# OctoSlime_Base_Unit.net
KiCad netlist of a schematic drawn in EasyEDA Pro
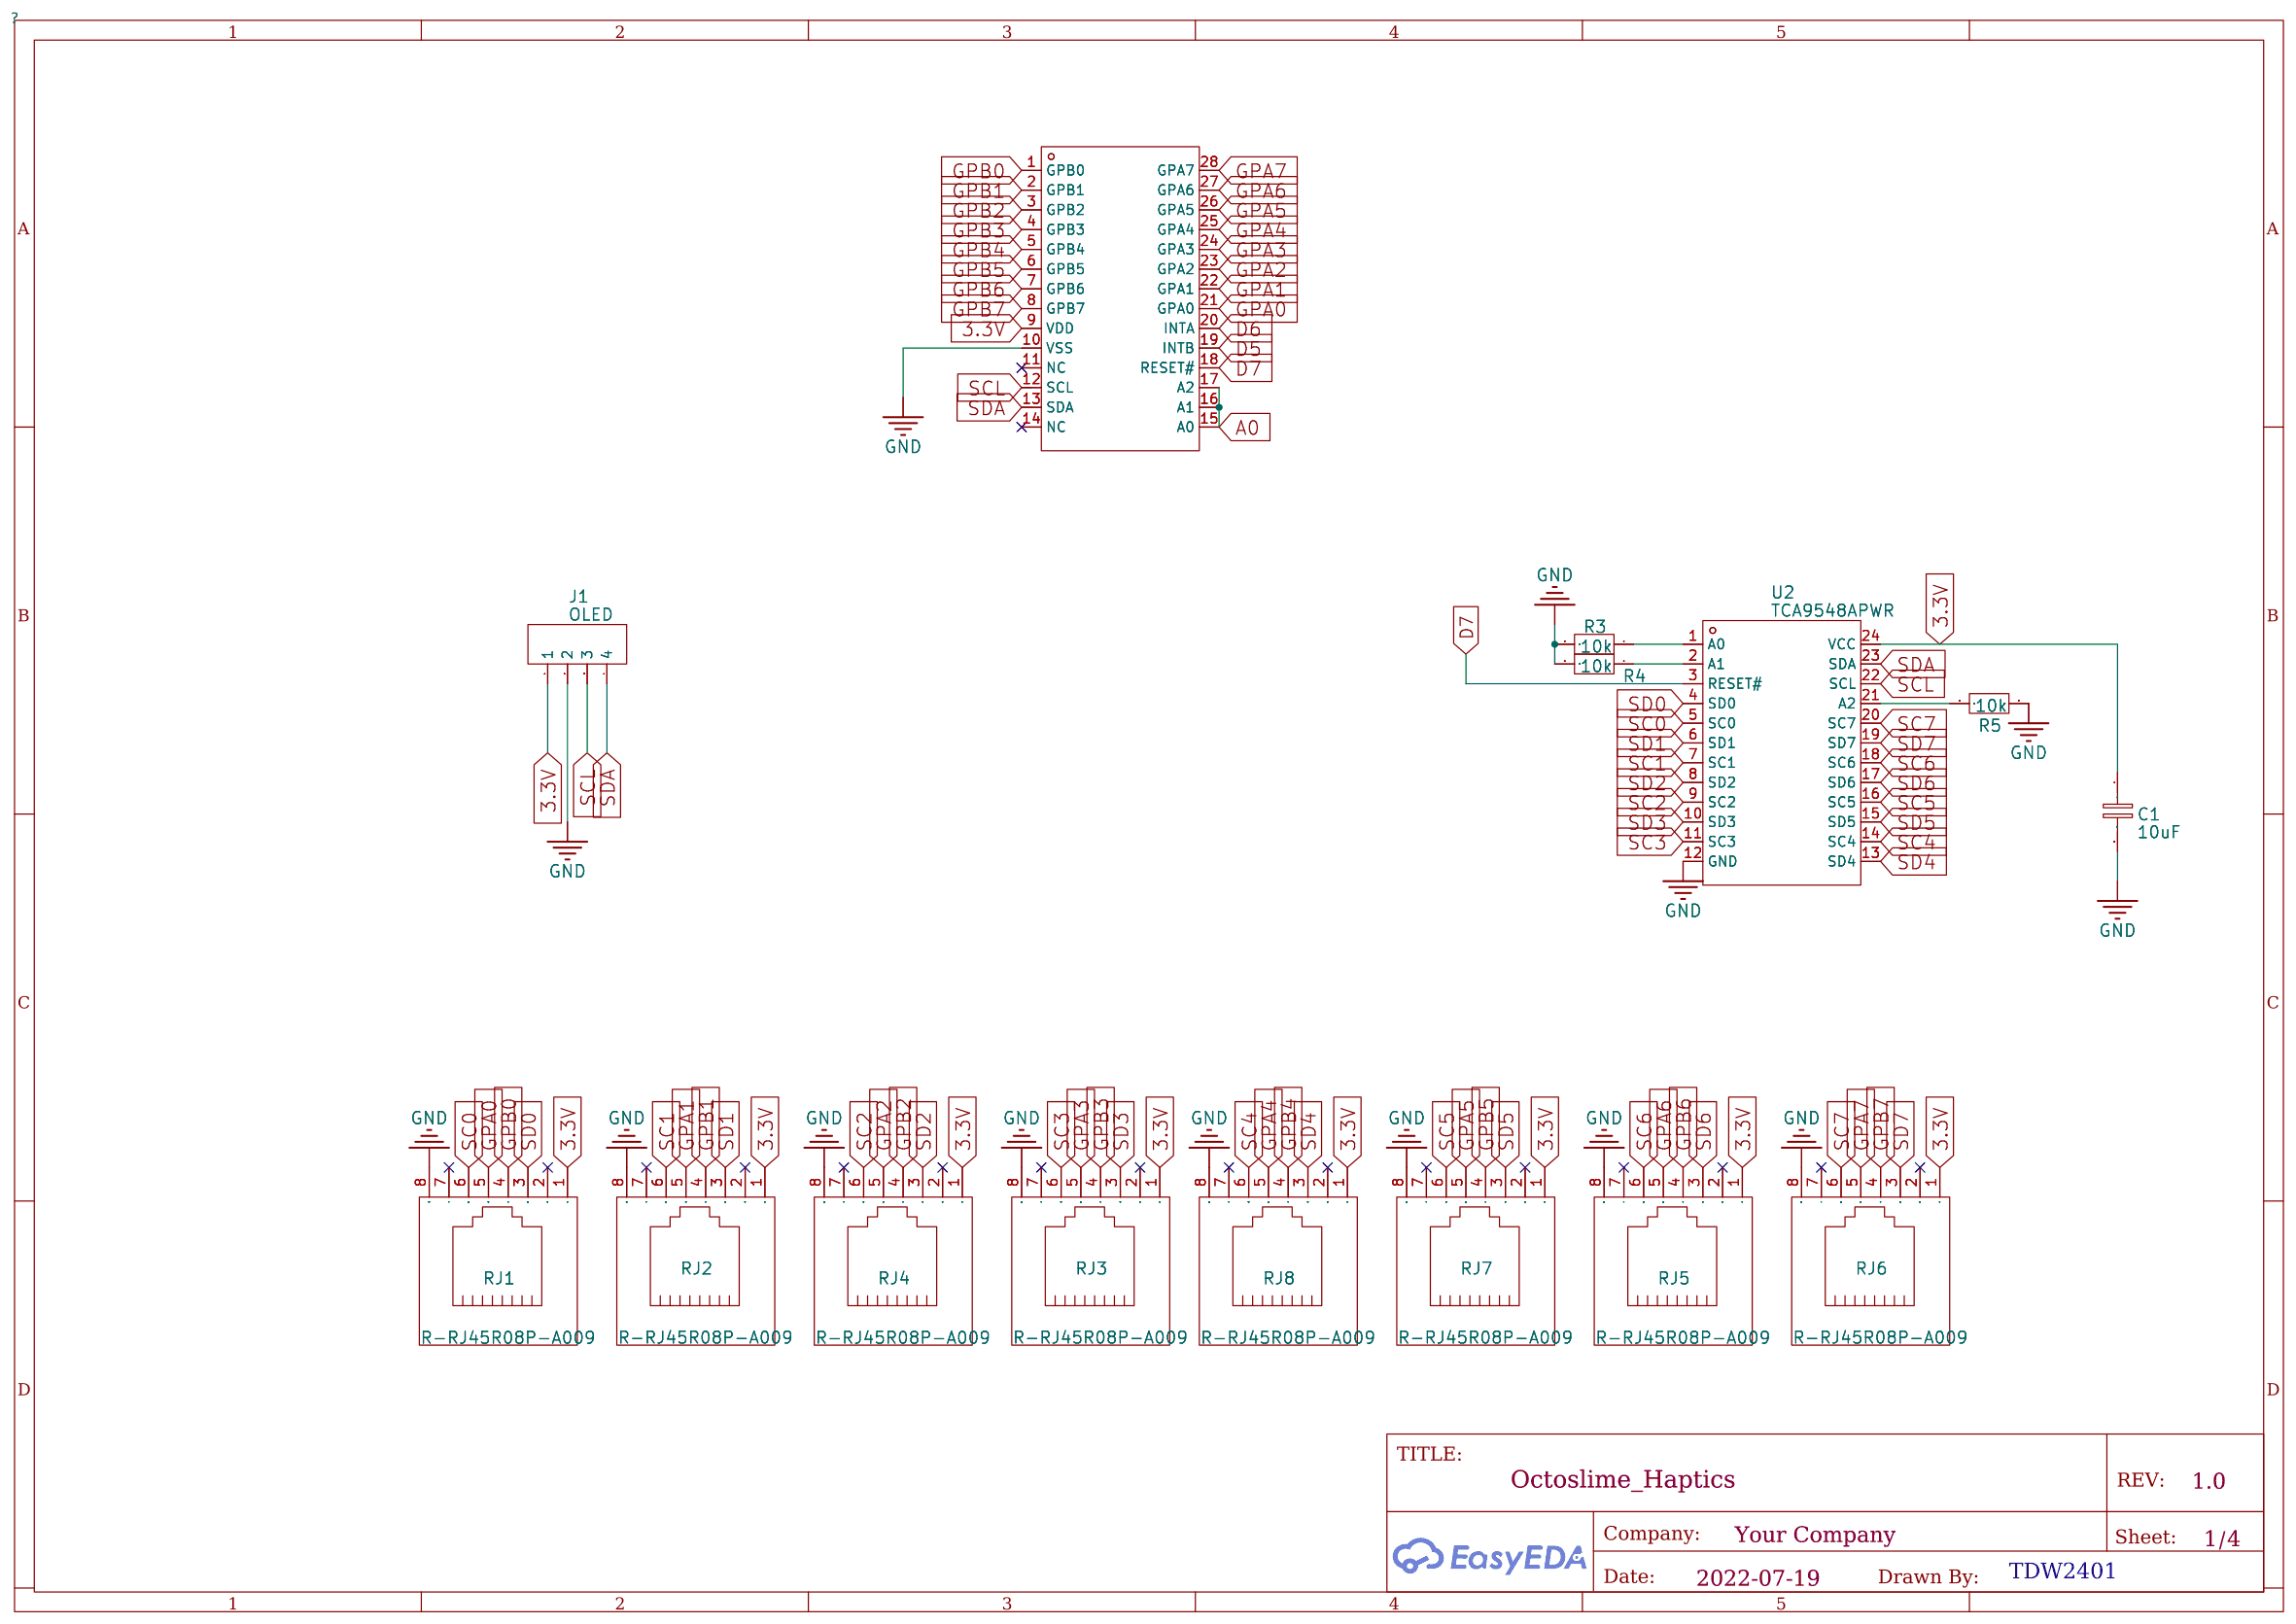
[diagram p0: I2C breakout and OLED]
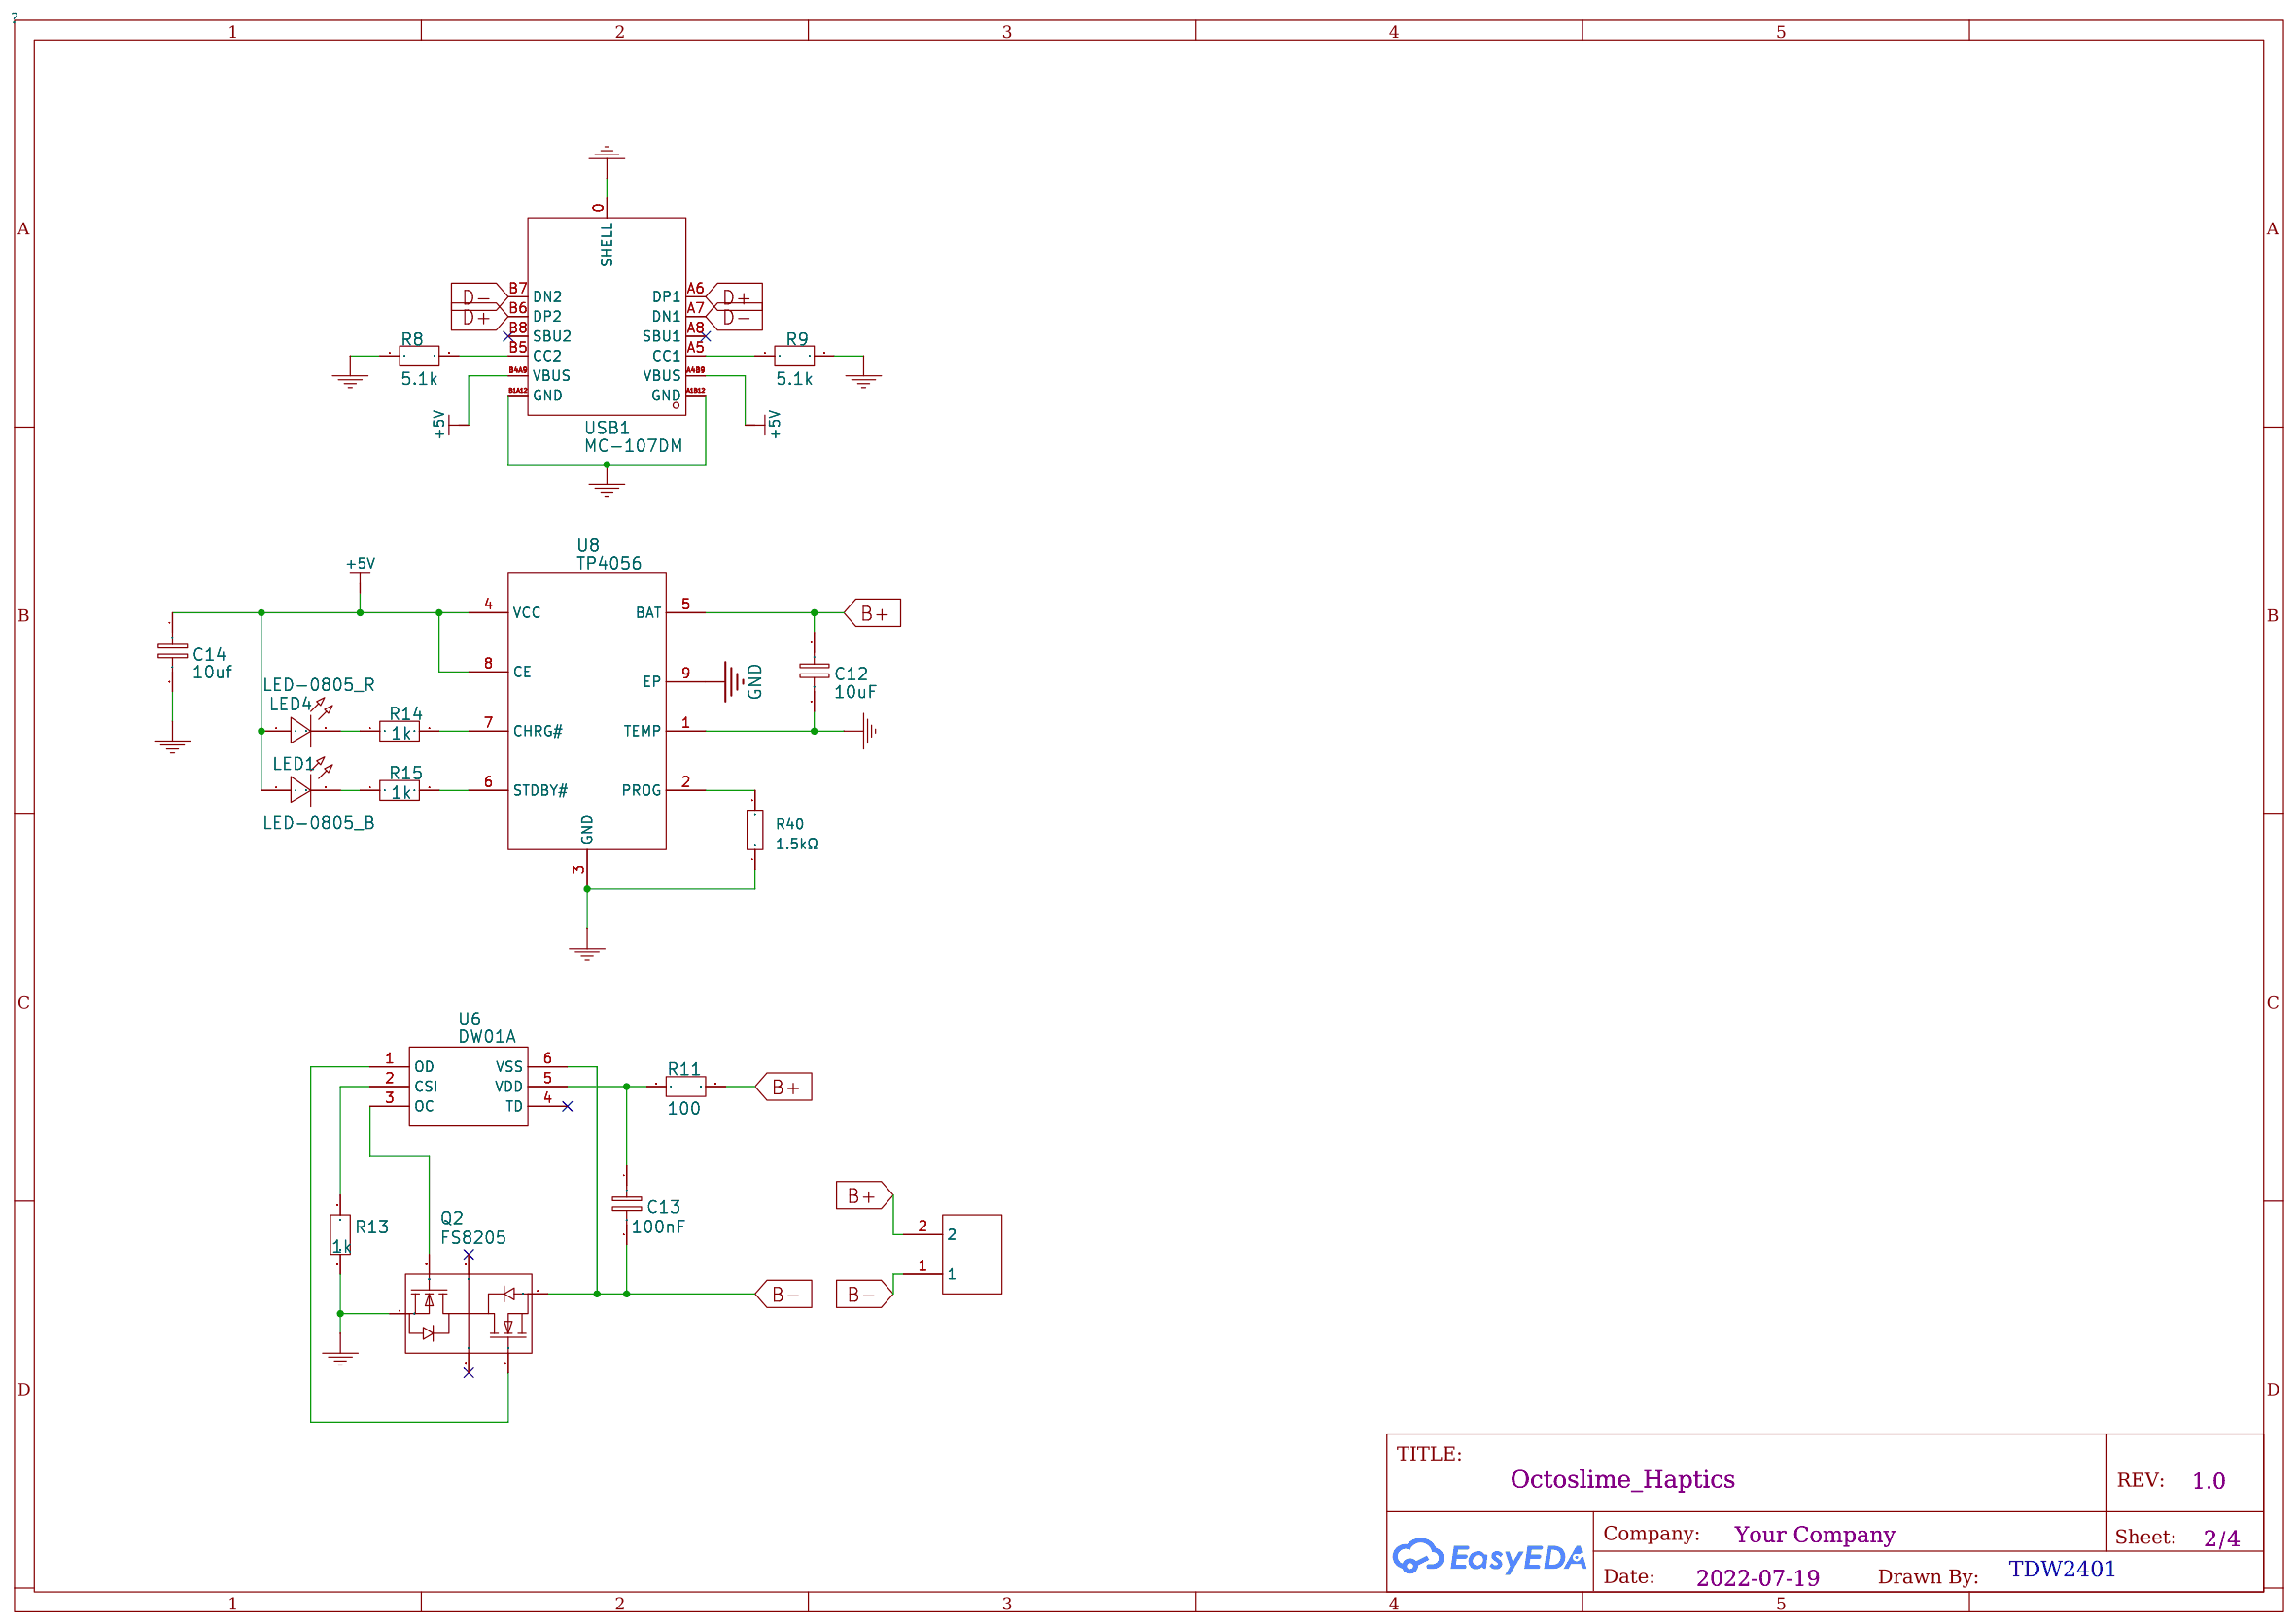
[diagram p1: Charge / data]
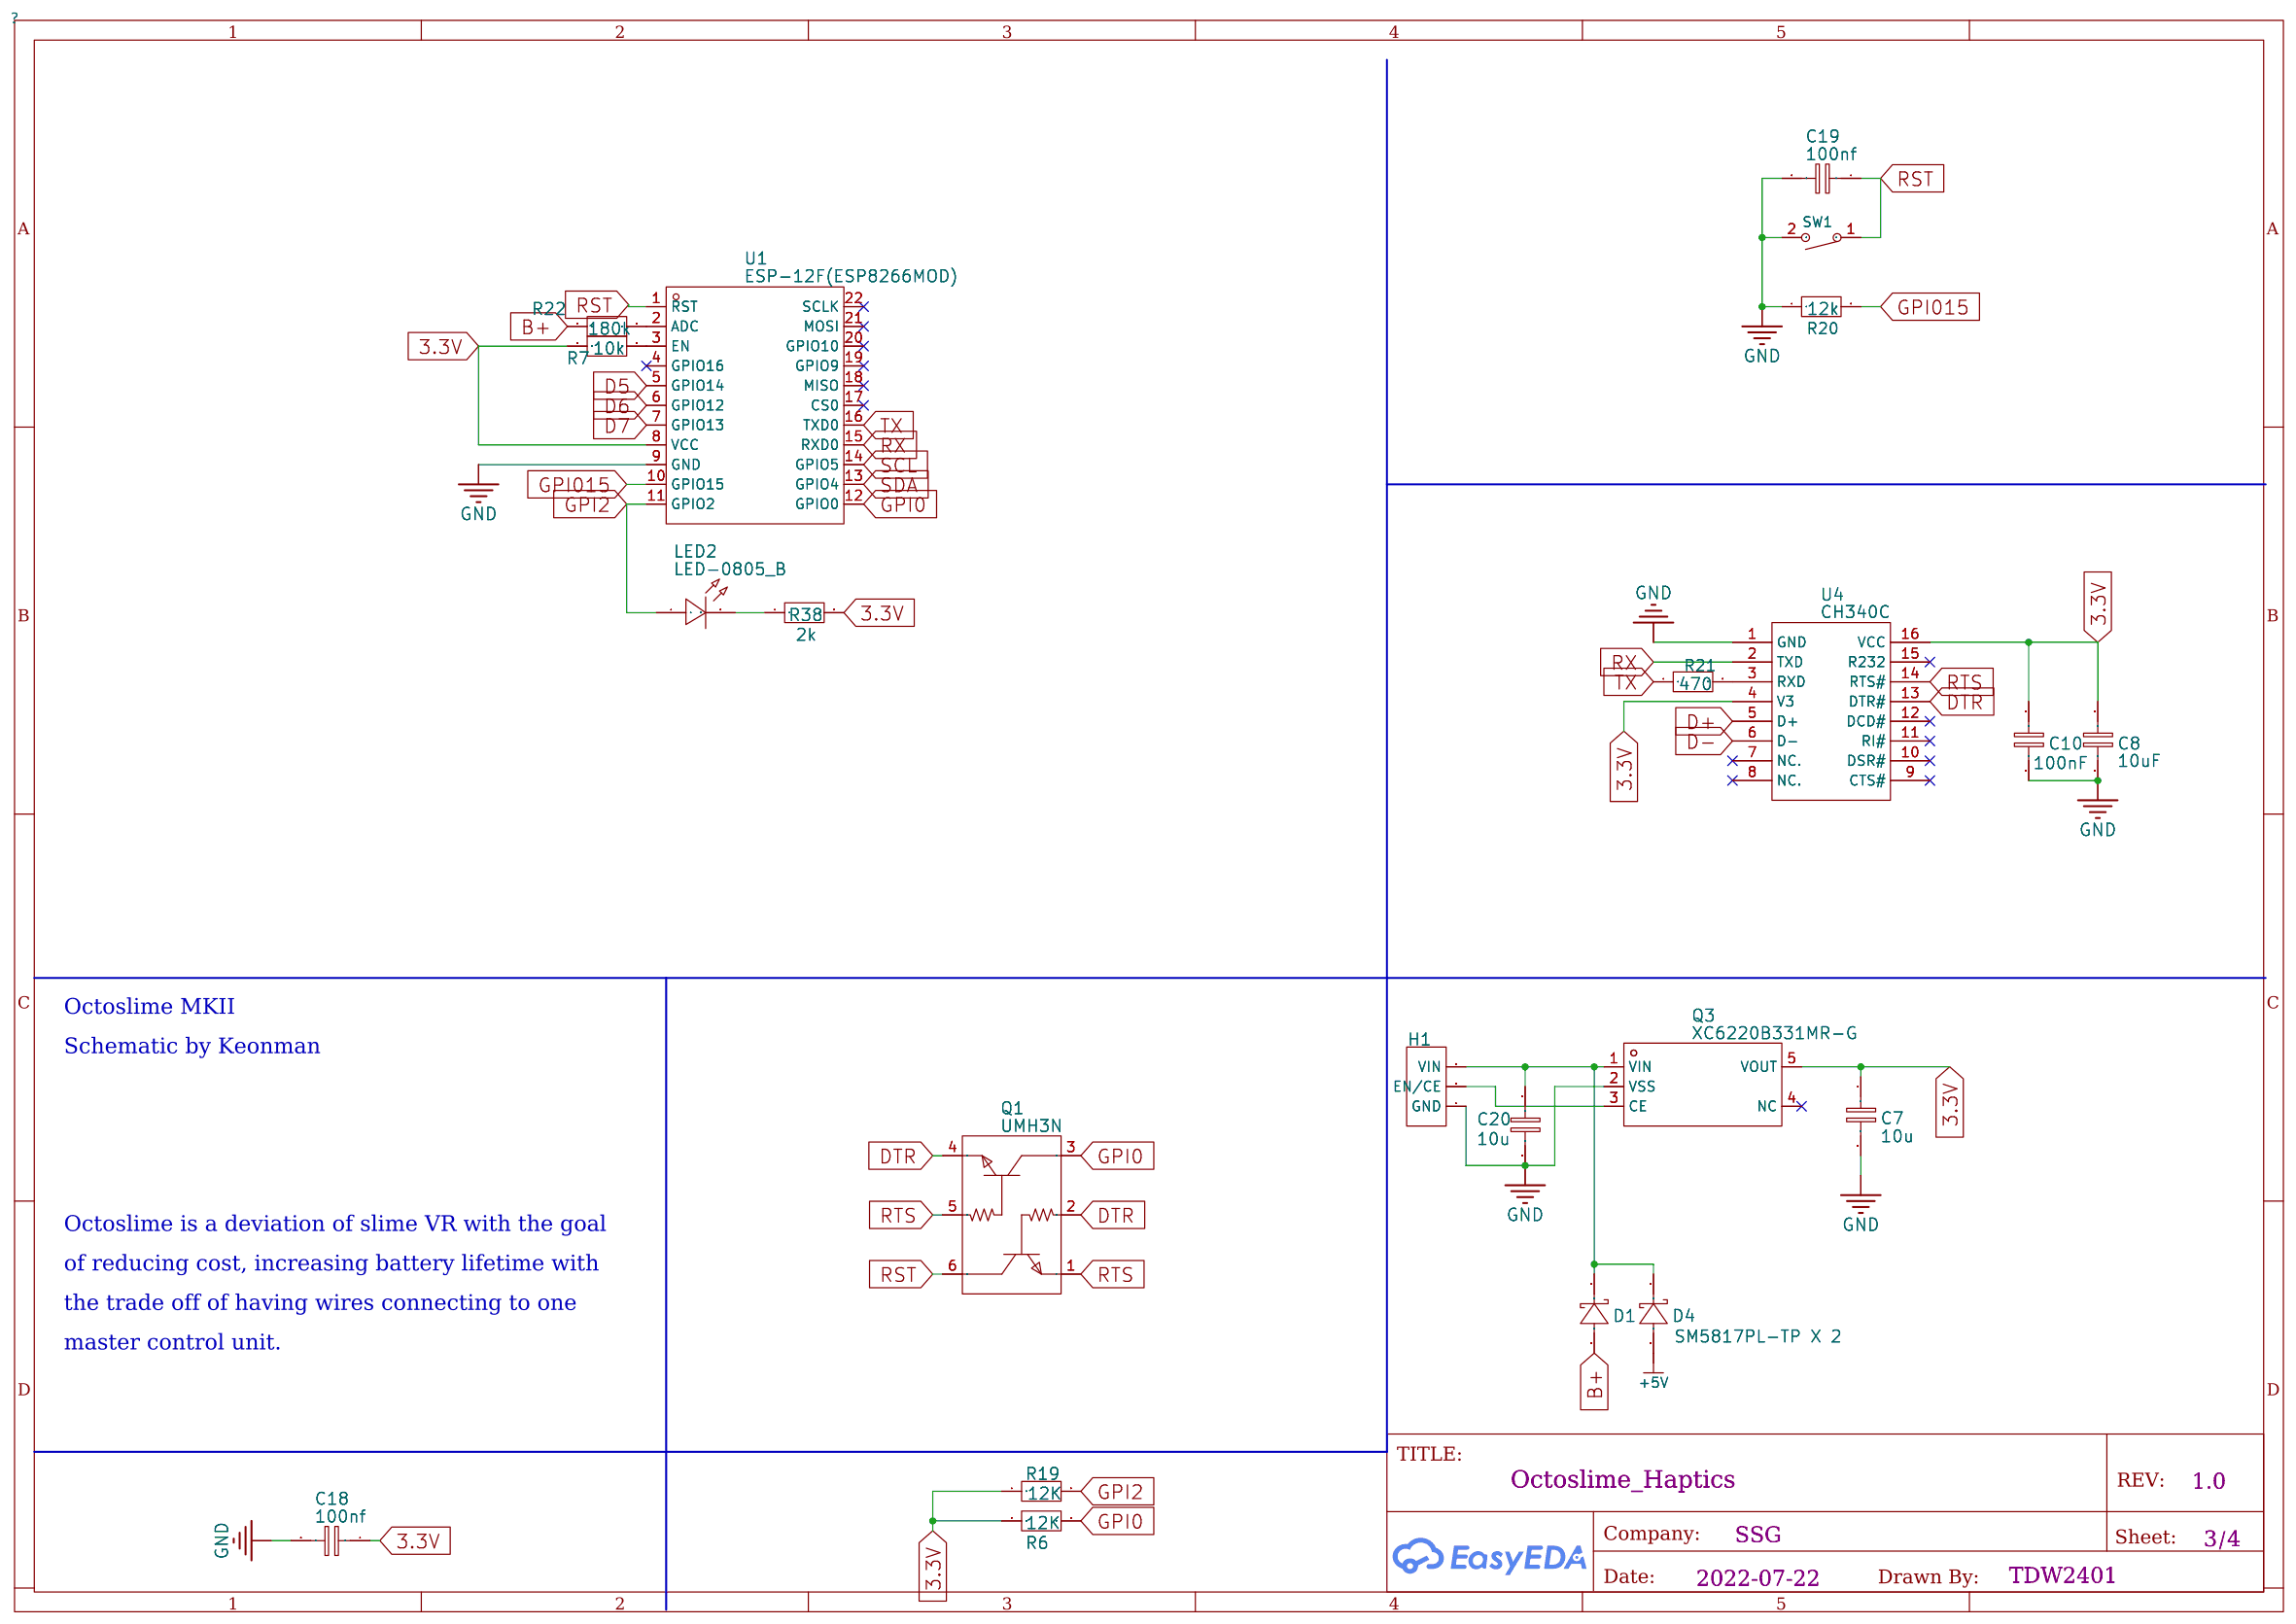
[diagram p2: MCU]
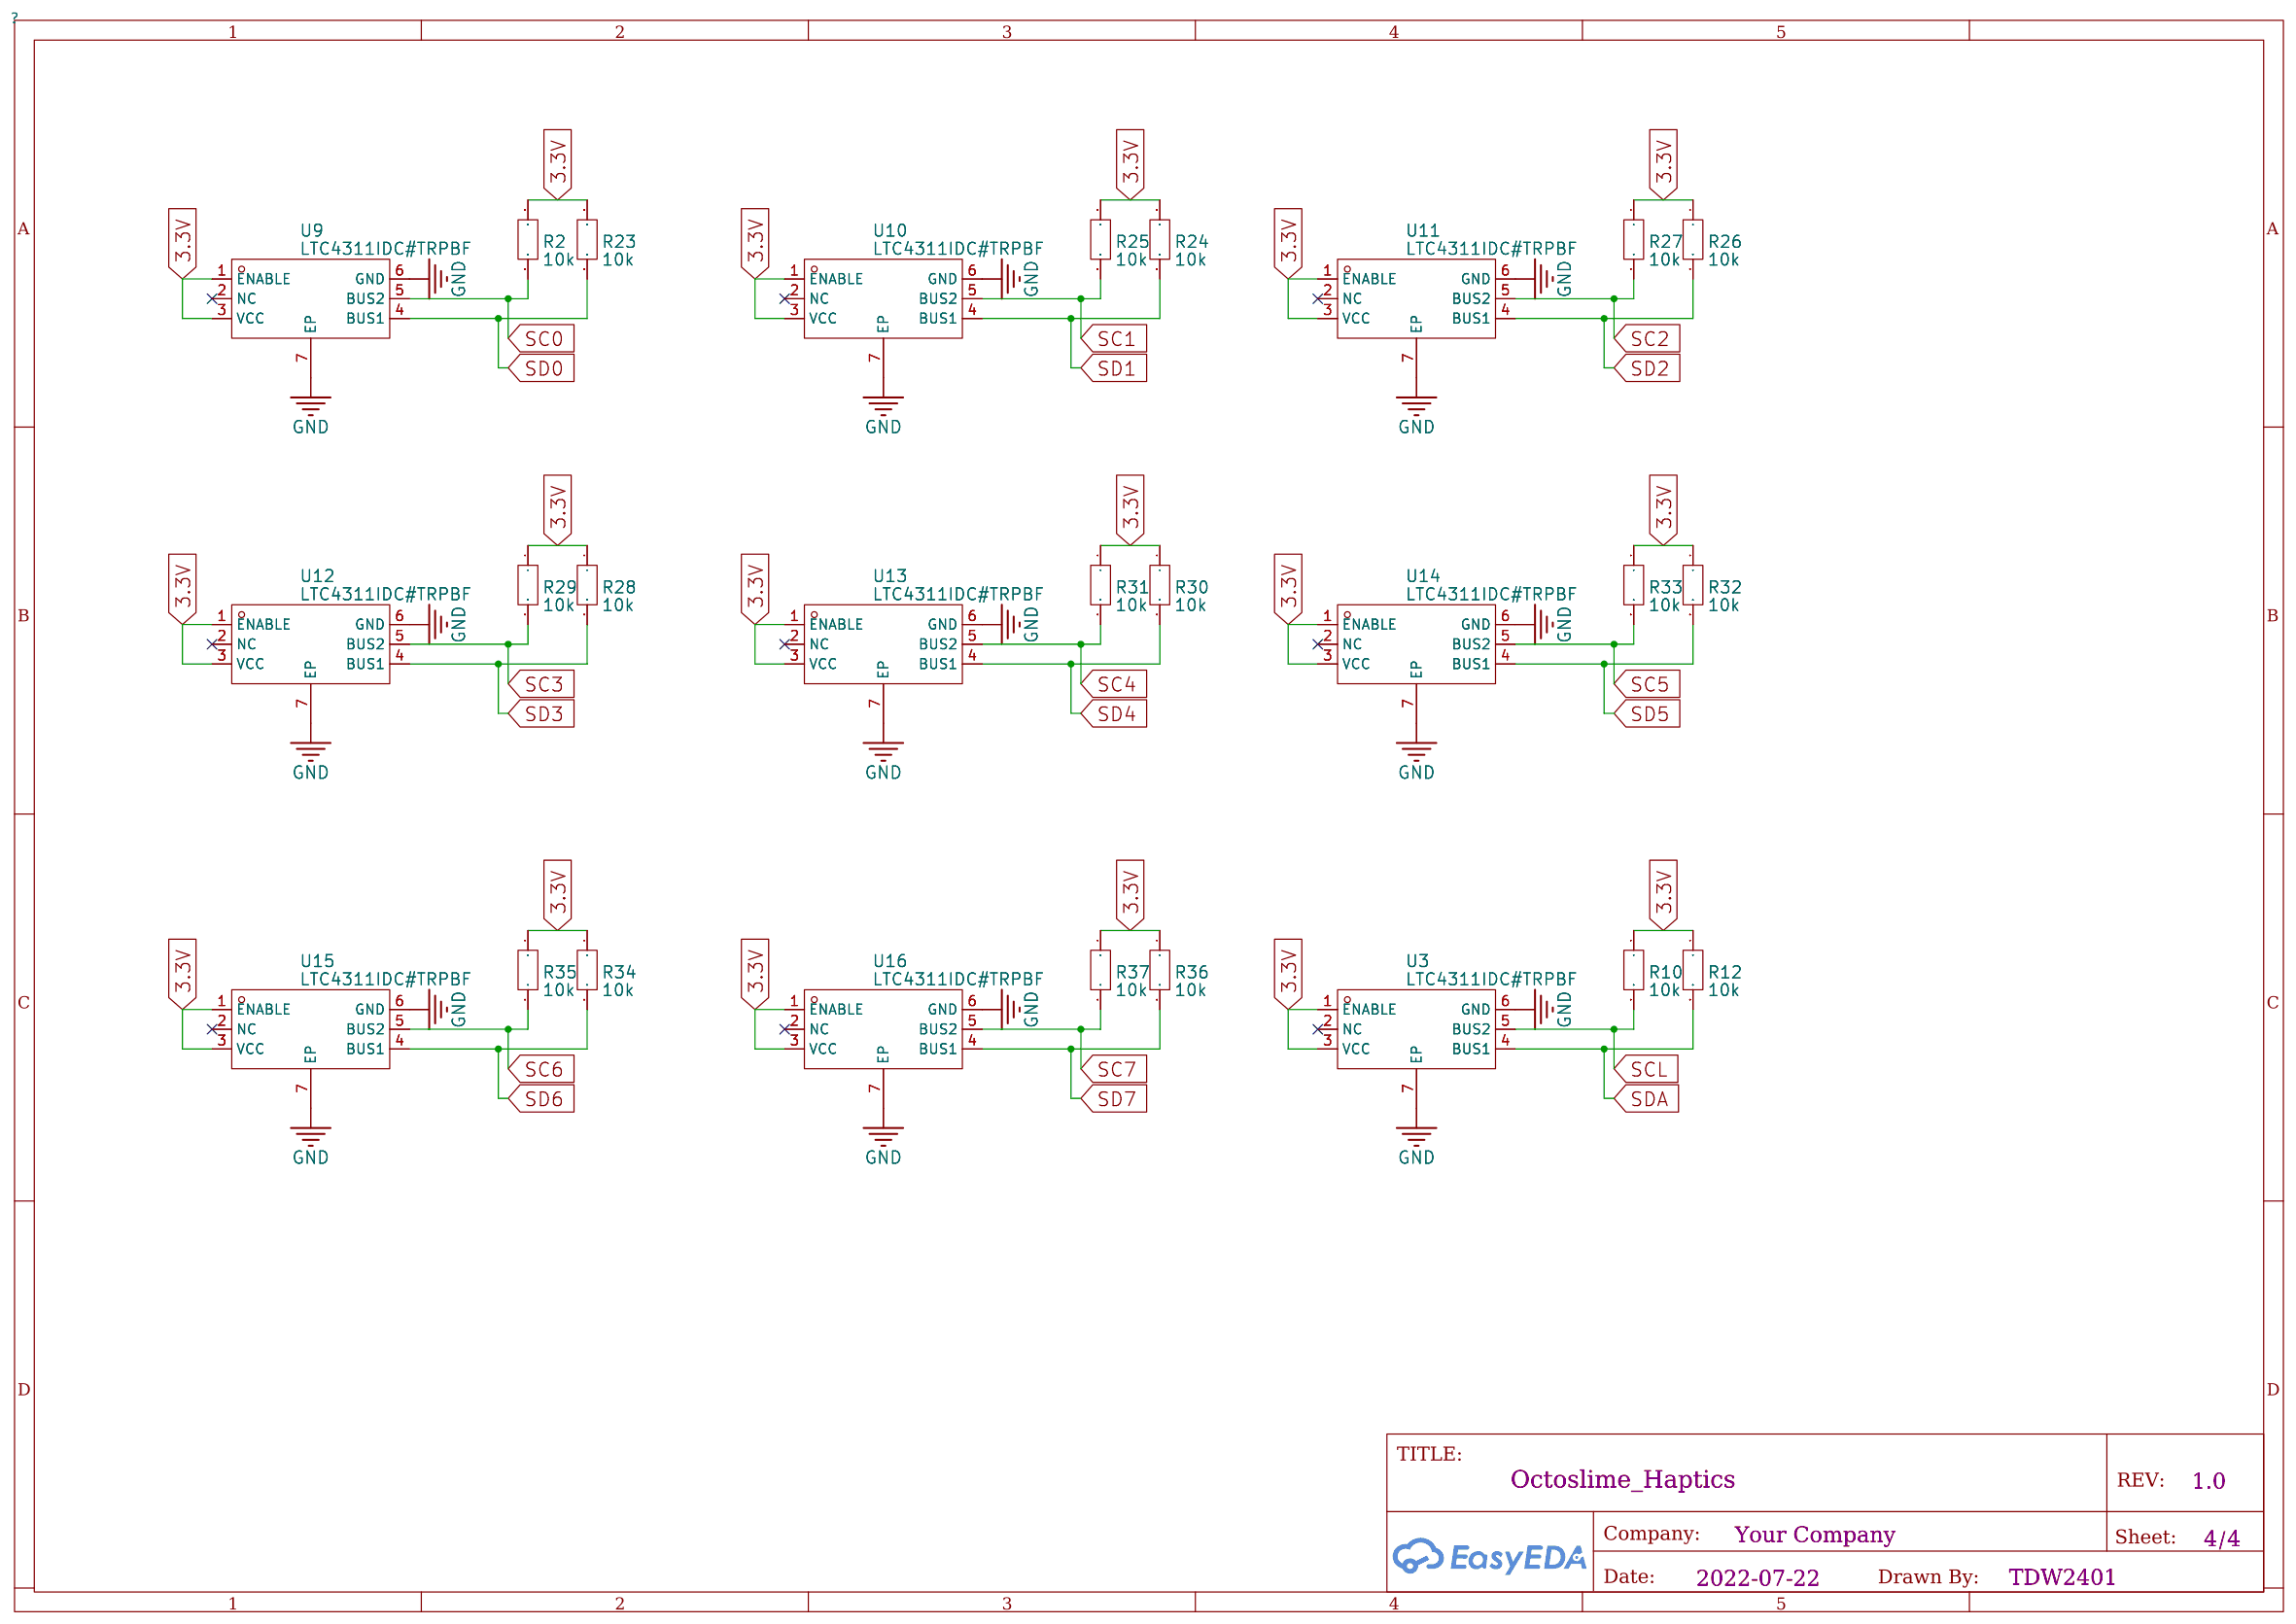
[diagram p3: I2C thing - ma - jigXC6220B331PR-G]

(export (version "E")
  (design (tool "Eeschema 10.0.6"))
  (components
    (comp (ref "C1")
      (value "10uF")
      (footprint "easyedapro:C0805")
      (libsource (lib "easyedapro") (part "10uF"))
    )
    (comp (ref "J1")
      (value "OLED")
      (footprint "easyedapro:HDR-M-2.54_1X4")
      (libsource (lib "easyedapro") (part "OLED"))
    )
    (comp (ref "R3") (value "10k") (footprint "easyedapro:R0805") (libsource (lib "easyedapro") (part "10k")))
    (comp (ref "R4") (value "10k") (footprint "easyedapro:R0805") (libsource (lib "easyedapro") (part "10k")))
    (comp (ref "R5") (value "10k") (footprint "easyedapro:R0805") (libsource (lib "easyedapro") (part "10k")))
    (comp (ref "RJ1")
      (value "R-RJ45R08P-A009")
      (footprint "easyedapro:RJ45-TH_R-RJ45R08P-A009")
      (fields (field (name "Manufacturer") "Ckmtw(灿科盟)"))
      (libsource (lib "easyedapro") (part "R-RJ45R08P-A009"))
    )
    (comp (ref "RJ2")
      (value "R-RJ45R08P-A009")
      (footprint "easyedapro:RJ45-TH_R-RJ45R08P-A009")
      (fields (field (name "Manufacturer") "Ckmtw(灿科盟)"))
      (libsource (lib "easyedapro") (part "R-RJ45R08P-A009"))
    )
    (comp (ref "RJ3")
      (value "R-RJ45R08P-A009")
      (footprint "easyedapro:RJ45-TH_R-RJ45R08P-A009")
      (fields (field (name "Manufacturer") "Ckmtw(灿科盟)"))
      (libsource (lib "easyedapro") (part "R-RJ45R08P-A009"))
    )
    (comp (ref "RJ4")
      (value "R-RJ45R08P-A009")
      (footprint "easyedapro:RJ45-TH_R-RJ45R08P-A009")
      (fields (field (name "Manufacturer") "Ckmtw(灿科盟)"))
      (libsource (lib "easyedapro") (part "R-RJ45R08P-A009"))
    )
    (comp (ref "RJ5")
      (value "R-RJ45R08P-A009")
      (footprint "easyedapro:RJ45-TH_R-RJ45R08P-A009")
      (fields (field (name "Manufacturer") "Ckmtw(灿科盟)"))
      (libsource (lib "easyedapro") (part "R-RJ45R08P-A009"))
    )
    (comp (ref "RJ6")
      (value "R-RJ45R08P-A009")
      (footprint "easyedapro:RJ45-TH_R-RJ45R08P-A009")
      (fields (field (name "Manufacturer") "Ckmtw(灿科盟)"))
      (libsource (lib "easyedapro") (part "R-RJ45R08P-A009"))
    )
    (comp (ref "RJ7")
      (value "R-RJ45R08P-A009")
      (footprint "easyedapro:RJ45-TH_R-RJ45R08P-A009")
      (fields (field (name "Manufacturer") "Ckmtw(灿科盟)"))
      (libsource (lib "easyedapro") (part "R-RJ45R08P-A009"))
    )
    (comp (ref "RJ8")
      (value "R-RJ45R08P-A009")
      (footprint "easyedapro:RJ45-TH_R-RJ45R08P-A009")
      (fields (field (name "Manufacturer") "Ckmtw(灿科盟)"))
      (libsource (lib "easyedapro") (part "R-RJ45R08P-A009"))
    )
    (comp (ref "U2")
      (value "TCA9548APWR")
      (footprint "easyedapro:TSSOP-24_L7.8-W4.4-P0.65-LS6.4-BL")
      (fields (field (name "Manufacturer") "TI"))
      (libsource (lib "easyedapro") (part "TCA9548APWR"))
    )
    (comp (ref "U7")
      (value "~")
      (footprint "easyedapro:SOIC-28_L18.0-W7.5-P1.27-LS10.3-BL")
      (fields
        (field (name "Manufacturer Part") "MCP23017-E/SO")
        (field (name "Manufacturer") "MICROCHIP(美国微芯)")
      )
      (libsource (lib "easyedapro") (part "MCP23017-E/SO"))
    )
    (comp (ref "C12")
      (value "10uF")
      (footprint "easyedapro:C0805")
      (libsource (lib "easyedapro") (part "10uF"))
    )
    (comp (ref "C13")
      (value "100nF")
      (footprint "easyedapro:C0805")
      (libsource (lib "easyedapro") (part "100nF"))
    )
    (comp (ref "C14")
      (value "10uf")
      (footprint "easyedapro:C0805")
      (libsource (lib "easyedapro") (part "10uf"))
    )
    (comp (ref "CN8")
      (value "B2B-PH-K-S(LF)(SN)")
      (footprint "easyedapro:CONN-TH_B2B-PH-K-S")
      (fields (field (name "Manufacturer") "JST"))
      (libsource (lib "easyedapro") (part "B2B-PH-K-S(LF)(SN)"))
    )
    (comp (ref "LED1")
      (value "LED-0805_B")
      (footprint "easyedapro:LED0805_BLUE")
      (fields (field (name "Manufacturer Part") "D-B080508B1-KS2") (field (name "Manufacturer") "方舟 ARKLED"))
      (libsource (lib "easyedapro") (part "LED-0805_B"))
    )
    (comp (ref "LED4")
      (value "LED-0805_R")
      (footprint "easyedapro:LED0805_RED")
      (fields
        (field (name "Manufacturer Part") "17-21SURC/S530-A3/TR8")
        (field (name "Manufacturer") "EVERLIGHT(台湾亿光)")
      )
      (libsource (lib "easyedapro") (part "LED-0805_R"))
    )
    (comp (ref "Q2")
      (value "FS8205")
      (footprint "easyedapro:SOT-23-6_L2.9-W1.6-P0.95-LS2.8-BR")
      (fields (field (name "Manufacturer") "FORTUNE"))
      (libsource (lib "easyedapro") (part "FS8205"))
    )
    (comp (ref "R8")
      (value "5.1k")
      (footprint "easyedapro:R0805")
      (libsource (lib "easyedapro") (part "5.1k"))
    )
    (comp (ref "R9")
      (value "5.1k")
      (footprint "easyedapro:R0805")
      (libsource (lib "easyedapro") (part "5.1k"))
    )
    (comp (ref "R11")
      (value "100")
      (footprint "easyedapro:R0805")
      (libsource (lib "easyedapro") (part "100"))
    )
    (comp (ref "R13") (value "1k") (footprint "easyedapro:R0805") (libsource (lib "easyedapro") (part "1k")))
    (comp (ref "R14") (value "1k") (footprint "easyedapro:R0805") (libsource (lib "easyedapro") (part "1k")))
    (comp (ref "R15") (value "1k") (footprint "easyedapro:R0805") (libsource (lib "easyedapro") (part "1k")))
    (comp (ref "R40")
      (value "1.5kΩ")
      (footprint "easyedapro:R0805")
      (description "电阻类型:厚膜电阻;阻值:1.5kΩ;精度:±1%;功率:125mW;温度系数:±100ppm/;最大工作电压:150V;工作温度范围:-55~+155;")
      (fields
        (field (name "Manufacturer Part") "0805W8F1501T5E")
        (field (name "Manufacturer") "UNI-ROYAL(厚声)")
      )
      (libsource (lib "easyedapro") (part "0805W8F1501T5E"))
    )
    (comp (ref "U6")
      (value "DW01A")
      (footprint "easyedapro:SOT-23-6_L2.9-W1.6-P0.95-LS2.8-BL")
      (fields (field (name "Manufacturer") "FM"))
      (libsource (lib "easyedapro") (part "DW01A"))
    )
    (comp (ref "U8")
      (value "TP4056")
      (footprint "easyedapro:ESOP-8_L4.9-W3.9-P1.27-LS6.0-BL-EP")
      (fields (field (name "Manufacturer") "TOPPOWER"))
      (libsource (lib "easyedapro") (part "TP4056"))
    )
    (comp (ref "USB1")
      (value "MC-107DM")
      (footprint "easyedapro:USB-C-SMD_MC-107D")
      (fields (field (name "Manufacturer") "台湾汉博"))
      (libsource (lib "easyedapro") (part "MC-107DM"))
    )
    (comp (ref "C7") (value "10u") (footprint "easyedapro:C0805") (libsource (lib "easyedapro") (part "10u")))
    (comp (ref "C8")
      (value "10uF")
      (footprint "easyedapro:C0805")
      (libsource (lib "easyedapro") (part "10uF"))
    )
    (comp (ref "C10")
      (value "100nF")
      (footprint "easyedapro:C0805")
      (libsource (lib "easyedapro") (part "100nF"))
    )
    (comp (ref "C18")
      (value "100nf")
      (footprint "easyedapro:C0805")
      (libsource (lib "easyedapro") (part "100nf"))
    )
    (comp (ref "C19")
      (value "100nf")
      (footprint "easyedapro:C0805")
      (libsource (lib "easyedapro") (part "100nf"))
    )
    (comp (ref "C20")
      (value "10u")
      (footprint "easyedapro:C0805")
      (libsource (lib "easyedapro") (part "10u"))
    )
    (comp (ref "D1")
      (value "SM5817PL-TP X 2")
      (footprint "easyedapro:SOD-123FL_L2.8-W1.7-LS3.6-RD")
      (fields
        (field (name "Manufacturer Part") "SM5817PL-TP")
        (field (name "Manufacturer") "MCC(Micro Commercial Components)")
      )
      (libsource (lib "easyedapro") (part "SM5817PL-TP X 2"))
    )
    (comp (ref "D4")
      (value "SM5817PL-TP X 2")
      (footprint "easyedapro:SOD-123FL_L2.8-W1.7-LS3.6-RD")
      (fields
        (field (name "Manufacturer Part") "SM5817PL-TP")
        (field (name "Manufacturer") "MCC(Micro Commercial Components)")
      )
      (libsource (lib "easyedapro") (part "SM5817PL-TP X 2"))
    )
    (comp (ref "H1")
      (value "HDR-F-2.54_1x3")
      (footprint "easyedapro:HDR-F-2.54_1X3")
      (libsource (lib "easyedapro") (part "HDR-F-2.54_1x3"))
    )
    (comp (ref "LED2")
      (value "LED-0805_B")
      (footprint "easyedapro:LED0805_BLUE")
      (fields (field (name "Manufacturer Part") "D-B080508B1-KS2") (field (name "Manufacturer") "方舟 ARKLED"))
      (libsource (lib "easyedapro") (part "LED-0805_B"))
    )
    (comp (ref "Q1")
      (value "UMH3N")
      (footprint "easyedapro:SC-70-6_L2.2-W1.3-P0.65-LS2.1-BR")
      (fields (field (name "Manufacturer") "CJ"))
      (libsource (lib "easyedapro") (part "UMH3N"))
    )
    (comp (ref "Q3")
      (value "XC6220B331MR-G")
      (footprint "easyedapro:SOT-25-5_L3.0-W1.8-P0.95-LS3.0-BR")
      (fields (field (name "Manufacturer") "TOREX"))
      (libsource (lib "easyedapro") (part "XC6220B331MR-G"))
    )
    (comp (ref "R6") (value "12K") (footprint "easyedapro:R0805") (libsource (lib "easyedapro") (part "12K")))
    (comp (ref "R7") (value "10k") (footprint "easyedapro:R0805") (libsource (lib "easyedapro") (part "10k")))
    (comp (ref "R19")
      (value "12K")
      (footprint "easyedapro:R0805")
      (libsource (lib "easyedapro") (part "12K"))
    )
    (comp (ref "R20")
      (value "12k")
      (footprint "easyedapro:R0805")
      (libsource (lib "easyedapro") (part "12k"))
    )
    (comp (ref "R21")
      (value "470")
      (footprint "easyedapro:R0805")
      (libsource (lib "easyedapro") (part "470"))
    )
    (comp (ref "R22")
      (value "180k")
      (footprint "easyedapro:R0805")
      (libsource (lib "easyedapro") (part "180k"))
    )
    (comp (ref "R38") (value "2k") (footprint "easyedapro:R0805") (libsource (lib "easyedapro") (part "2k")))
    (comp (ref "SW1")
      (value "~")
      (footprint "easyedapro:SW-SMD_L4.0-W2.9-LS5.0")
      (fields (field (name "Manufacturer Part") "TS342A2P-WZ") (field (name "Manufacturer") "SHOU HAN(首韩)"))
      (libsource (lib "easyedapro") (part "TS342A2P-WZ"))
    )
    (comp (ref "U1")
      (value "ESP-12F(ESP8266MOD)")
      (footprint "easyedapro:WIFIM-SMD_ESP-12F-ESP8266MOD")
      (fields (field (name "Manufacturer") "Ai-Thinker"))
      (libsource (lib "easyedapro") (part "ESP-12F(ESP8266MOD)"))
    )
    (comp (ref "U4")
      (value "CH340C")
      (footprint "easyedapro:SOP-16_L10.0-W3.9-P1.27-LS6.0-BL")
      (fields (field (name "Manufacturer") "WCH"))
      (libsource (lib "easyedapro") (part "CH340C"))
    )
    (comp (ref "R2") (value "10k") (footprint "easyedapro:R0805") (libsource (lib "easyedapro") (part "10k")))
    (comp (ref "R10")
      (value "10k")
      (footprint "easyedapro:R0805")
      (libsource (lib "easyedapro") (part "10k"))
    )
    (comp (ref "R12")
      (value "10k")
      (footprint "easyedapro:R0805")
      (libsource (lib "easyedapro") (part "10k"))
    )
    (comp (ref "R23")
      (value "10k")
      (footprint "easyedapro:R0805")
      (libsource (lib "easyedapro") (part "10k"))
    )
    (comp (ref "R24")
      (value "10k")
      (footprint "easyedapro:R0805")
      (libsource (lib "easyedapro") (part "10k"))
    )
    (comp (ref "R25")
      (value "10k")
      (footprint "easyedapro:R0805")
      (libsource (lib "easyedapro") (part "10k"))
    )
    (comp (ref "R26")
      (value "10k")
      (footprint "easyedapro:R0805")
      (libsource (lib "easyedapro") (part "10k"))
    )
    (comp (ref "R27")
      (value "10k")
      (footprint "easyedapro:R0805")
      (libsource (lib "easyedapro") (part "10k"))
    )
    (comp (ref "R28")
      (value "10k")
      (footprint "easyedapro:R0805")
      (libsource (lib "easyedapro") (part "10k"))
    )
    (comp (ref "R29")
      (value "10k")
      (footprint "easyedapro:R0805")
      (libsource (lib "easyedapro") (part "10k"))
    )
    (comp (ref "R30")
      (value "10k")
      (footprint "easyedapro:R0805")
      (libsource (lib "easyedapro") (part "10k"))
    )
    (comp (ref "R31")
      (value "10k")
      (footprint "easyedapro:R0805")
      (libsource (lib "easyedapro") (part "10k"))
    )
    (comp (ref "R32")
      (value "10k")
      (footprint "easyedapro:R0805")
      (libsource (lib "easyedapro") (part "10k"))
    )
    (comp (ref "R33")
      (value "10k")
      (footprint "easyedapro:R0805")
      (libsource (lib "easyedapro") (part "10k"))
    )
    (comp (ref "R34")
      (value "10k")
      (footprint "easyedapro:R0805")
      (libsource (lib "easyedapro") (part "10k"))
    )
    (comp (ref "R35")
      (value "10k")
      (footprint "easyedapro:R0805")
      (libsource (lib "easyedapro") (part "10k"))
    )
    (comp (ref "R36")
      (value "10k")
      (footprint "easyedapro:R0805")
      (libsource (lib "easyedapro") (part "10k"))
    )
    (comp (ref "R37")
      (value "10k")
      (footprint "easyedapro:R0805")
      (libsource (lib "easyedapro") (part "10k"))
    )
    (comp (ref "U3")
      (value "LTC4311IDC#TRPBF")
      (footprint "easyedapro:DFN-6_L2.0-W2.0-P0.50-BL-EP")
      (fields (field (name "Manufacturer") "Analog Devices"))
      (libsource (lib "easyedapro") (part "LTC4311IDC#TRPBF"))
    )
    (comp (ref "U9")
      (value "LTC4311IDC#TRPBF")
      (footprint "easyedapro:DFN-6_L2.0-W2.0-P0.50-BL-EP")
      (fields (field (name "Manufacturer") "Analog Devices"))
      (libsource (lib "easyedapro") (part "LTC4311IDC#TRPBF"))
    )
    (comp (ref "U10")
      (value "LTC4311IDC#TRPBF")
      (footprint "easyedapro:DFN-6_L2.0-W2.0-P0.50-BL-EP")
      (fields (field (name "Manufacturer") "Analog Devices"))
      (libsource (lib "easyedapro") (part "LTC4311IDC#TRPBF"))
    )
    (comp (ref "U11")
      (value "LTC4311IDC#TRPBF")
      (footprint "easyedapro:DFN-6_L2.0-W2.0-P0.50-BL-EP")
      (fields (field (name "Manufacturer") "Analog Devices"))
      (libsource (lib "easyedapro") (part "LTC4311IDC#TRPBF"))
    )
    (comp (ref "U12")
      (value "LTC4311IDC#TRPBF")
      (footprint "easyedapro:DFN-6_L2.0-W2.0-P0.50-BL-EP")
      (fields (field (name "Manufacturer") "Analog Devices"))
      (libsource (lib "easyedapro") (part "LTC4311IDC#TRPBF"))
    )
    (comp (ref "U13")
      (value "LTC4311IDC#TRPBF")
      (footprint "easyedapro:DFN-6_L2.0-W2.0-P0.50-BL-EP")
      (fields (field (name "Manufacturer") "Analog Devices"))
      (libsource (lib "easyedapro") (part "LTC4311IDC#TRPBF"))
    )
    (comp (ref "U14")
      (value "LTC4311IDC#TRPBF")
      (footprint "easyedapro:DFN-6_L2.0-W2.0-P0.50-BL-EP")
      (fields (field (name "Manufacturer") "Analog Devices"))
      (libsource (lib "easyedapro") (part "LTC4311IDC#TRPBF"))
    )
    (comp (ref "U15")
      (value "LTC4311IDC#TRPBF")
      (footprint "easyedapro:DFN-6_L2.0-W2.0-P0.50-BL-EP")
      (fields (field (name "Manufacturer") "Analog Devices"))
      (libsource (lib "easyedapro") (part "LTC4311IDC#TRPBF"))
    )
    (comp (ref "U16")
      (value "LTC4311IDC#TRPBF")
      (footprint "easyedapro:DFN-6_L2.0-W2.0-P0.50-BL-EP")
      (fields (field (name "Manufacturer") "Analog Devices"))
      (libsource (lib "easyedapro") (part "LTC4311IDC#TRPBF"))
    )
  )
  (nets
    (net (code "1") (name "+5V") (class "Default")
      (node (ref "C14") (pin "1") (pinfunction "1_1") (pintype "input"))
      (node (ref "D4") (pin "2") (pinfunction "A_2") (pintype "input"))
      (node (ref "LED1") (pin "1") (pinfunction "1_1") (pintype "input"))
      (node (ref "LED4") (pin "1") (pinfunction "1_1") (pintype "input"))
      (node (ref "U8") (pin "4") (pinfunction "VCC_4") (pintype "input"))
      (node (ref "U8") (pin "8") (pinfunction "CE_8") (pintype "input"))
      (node (ref "USB1") (pin "A4B9") (pinfunction "VBUS_A4B9") (pintype "input"))
      (node (ref "USB1") (pin "B4A9") (pinfunction "VBUS_B4A9") (pintype "input"))
    )
    (net (code "2") (name "3.3V") (class "Default")
      (node (ref "C1") (pin "1") (pinfunction "1_1") (pintype "input"))
      (node (ref "C10") (pin "1") (pinfunction "1_1") (pintype "input"))
      (node (ref "C18") (pin "1") (pinfunction "1_1") (pintype "input"))
      (node (ref "C7") (pin "1") (pinfunction "1_1") (pintype "input"))
      (node (ref "C8") (pin "1") (pinfunction "1_1") (pintype "input"))
      (node (ref "J1") (pin "1") (pinfunction "1_1") (pintype "input"))
      (node (ref "Q3") (pin "5") (pinfunction "VOUT_5") (pintype "input"))
      (node (ref "R10") (pin "1") (pinfunction "1_1") (pintype "input"))
      (node (ref "R12") (pin "1") (pinfunction "1_1") (pintype "input"))
      (node (ref "R19") (pin "1") (pinfunction "1_1") (pintype "input"))
      (node (ref "R2") (pin "1") (pinfunction "1_1") (pintype "input"))
      (node (ref "R23") (pin "1") (pinfunction "1_1") (pintype "input"))
      (node (ref "R24") (pin "1") (pinfunction "1_1") (pintype "input"))
      (node (ref "R25") (pin "1") (pinfunction "1_1") (pintype "input"))
      (node (ref "R26") (pin "1") (pinfunction "1_1") (pintype "input"))
      (node (ref "R27") (pin "1") (pinfunction "1_1") (pintype "input"))
      (node (ref "R28") (pin "1") (pinfunction "1_1") (pintype "input"))
      (node (ref "R29") (pin "1") (pinfunction "1_1") (pintype "input"))
      (node (ref "R30") (pin "1") (pinfunction "1_1") (pintype "input"))
      (node (ref "R31") (pin "1") (pinfunction "1_1") (pintype "input"))
      (node (ref "R32") (pin "1") (pinfunction "1_1") (pintype "input"))
      (node (ref "R33") (pin "1") (pinfunction "1_1") (pintype "input"))
      (node (ref "R34") (pin "1") (pinfunction "1_1") (pintype "input"))
      (node (ref "R35") (pin "1") (pinfunction "1_1") (pintype "input"))
      (node (ref "R36") (pin "1") (pinfunction "1_1") (pintype "input"))
      (node (ref "R37") (pin "1") (pinfunction "1_1") (pintype "input"))
      (node (ref "R38") (pin "2") (pinfunction "2_2") (pintype "input"))
      (node (ref "R6") (pin "1") (pinfunction "1_1") (pintype "input"))
      (node (ref "R7") (pin "1") (pinfunction "1_1") (pintype "input"))
      (node (ref "RJ1") (pin "1") (pinfunction "1_1") (pintype "input"))
      (node (ref "RJ2") (pin "1") (pinfunction "1_1") (pintype "input"))
      (node (ref "RJ3") (pin "1") (pinfunction "1_1") (pintype "input"))
      (node (ref "RJ4") (pin "1") (pinfunction "1_1") (pintype "input"))
      (node (ref "RJ5") (pin "1") (pinfunction "1_1") (pintype "input"))
      (node (ref "RJ6") (pin "1") (pinfunction "1_1") (pintype "input"))
      (node (ref "RJ7") (pin "1") (pinfunction "1_1") (pintype "input"))
      (node (ref "RJ8") (pin "1") (pinfunction "1_1") (pintype "input"))
      (node (ref "U1") (pin "8") (pinfunction "VCC_8") (pintype "input"))
      (node (ref "U10") (pin "1") (pinfunction "ENABLE_1") (pintype "input"))
      (node (ref "U10") (pin "3") (pinfunction "VCC_3") (pintype "input"))
      (node (ref "U11") (pin "1") (pinfunction "ENABLE_1") (pintype "input"))
      (node (ref "U11") (pin "3") (pinfunction "VCC_3") (pintype "input"))
      (node (ref "U12") (pin "1") (pinfunction "ENABLE_1") (pintype "input"))
      (node (ref "U12") (pin "3") (pinfunction "VCC_3") (pintype "input"))
      (node (ref "U13") (pin "1") (pinfunction "ENABLE_1") (pintype "input"))
      (node (ref "U13") (pin "3") (pinfunction "VCC_3") (pintype "input"))
      (node (ref "U14") (pin "1") (pinfunction "ENABLE_1") (pintype "input"))
      (node (ref "U14") (pin "3") (pinfunction "VCC_3") (pintype "input"))
      (node (ref "U15") (pin "1") (pinfunction "ENABLE_1") (pintype "input"))
      (node (ref "U15") (pin "3") (pinfunction "VCC_3") (pintype "input"))
      (node (ref "U16") (pin "1") (pinfunction "ENABLE_1") (pintype "input"))
      (node (ref "U16") (pin "3") (pinfunction "VCC_3") (pintype "input"))
      (node (ref "U2") (pin "24") (pinfunction "VCC_24") (pintype "input"))
      (node (ref "U3") (pin "1") (pinfunction "ENABLE_1") (pintype "input"))
      (node (ref "U3") (pin "3") (pinfunction "VCC_3") (pintype "input"))
      (node (ref "U4") (pin "16") (pinfunction "VCC_16") (pintype "input"))
      (node (ref "U4") (pin "4") (pinfunction "V3_4") (pintype "input"))
      (node (ref "U7") (pin "9") (pinfunction "VDD_9") (pintype "input"))
      (node (ref "U9") (pin "1") (pinfunction "ENABLE_1") (pintype "input"))
      (node (ref "U9") (pin "3") (pinfunction "VCC_3") (pintype "input"))
    )
    (net (code "3") (name "A0") (class "Default")
      (node (ref "U7") (pin "15") (pinfunction "A0_15") (pintype "input"))
      (node (ref "U7") (pin "16") (pinfunction "A1_16") (pintype "input"))
      (node (ref "U7") (pin "17") (pinfunction "A2_17") (pintype "input"))
    )
    (net (code "4") (name "B+") (class "Default")
      (node (ref "C12") (pin "1") (pinfunction "1_1") (pintype "input"))
      (node (ref "CN8") (pin "2") (pinfunction "2_2") (pintype "input"))
      (node (ref "D1") (pin "2") (pinfunction "A_2") (pintype "input"))
      (node (ref "R11") (pin "2") (pinfunction "2_2") (pintype "input"))
      (node (ref "R22") (pin "1") (pinfunction "1_1") (pintype "input"))
      (node (ref "U8") (pin "5") (pinfunction "BAT_5") (pintype "input"))
    )
    (net (code "5") (name "B-") (class "Default")
      (node (ref "C13") (pin "2") (pinfunction "2_2") (pintype "input"))
      (node (ref "CN8") (pin "1") (pinfunction "1_1") (pintype "input"))
      (node (ref "Q2") (pin "3") (pinfunction "S2_3") (pintype "input"))
      (node (ref "U6") (pin "6") (pinfunction "VSS_6") (pintype "input"))
    )
    (net (code "6") (name "D+") (class "Default")
      (node (ref "U4") (pin "5") (pinfunction "D+_5") (pintype "input"))
      (node (ref "USB1") (pin "A6") (pinfunction "DP1_A6") (pintype "input"))
      (node (ref "USB1") (pin "B6") (pinfunction "DP2_B6") (pintype "input"))
    )
    (net (code "7") (name "D-") (class "Default")
      (node (ref "U4") (pin "6") (pinfunction "D-_6") (pintype "input"))
      (node (ref "USB1") (pin "A7") (pinfunction "DN1_A7") (pintype "input"))
      (node (ref "USB1") (pin "B7") (pinfunction "DN2_B7") (pintype "input"))
    )
    (net (code "8") (name "D5") (class "Default")
      (node (ref "U1") (pin "5") (pinfunction "GPIO14_5") (pintype "input"))
      (node (ref "U7") (pin "19") (pinfunction "INTB_19") (pintype "input"))
    )
    (net (code "9") (name "D6") (class "Default")
      (node (ref "U1") (pin "6") (pinfunction "GPIO12_6") (pintype "input"))
      (node (ref "U7") (pin "20") (pinfunction "INTA_20") (pintype "input"))
    )
    (net (code "10") (name "D7") (class "Default")
      (node (ref "U1") (pin "7") (pinfunction "GPIO13_7") (pintype "input"))
      (node (ref "U2") (pin "3") (pinfunction "RESET#_3") (pintype "input"))
      (node (ref "U7") (pin "18") (pinfunction "RESET#_18") (pintype "input"))
    )
    (net (code "11") (name "DTR") (class "Default")
      (node (ref "Q1") (pin "2") (pinfunction "B_2") (pintype "input"))
      (node (ref "Q1") (pin "4") (pinfunction "E_4") (pintype "input"))
      (node (ref "U4") (pin "13") (pinfunction "DTR#_13") (pintype "input"))
    )
    (net (code "12") (name "GND") (class "Default")
      (node (ref "C1") (pin "2") (pinfunction "2_2") (pintype "input"))
      (node (ref "C10") (pin "2") (pinfunction "2_2") (pintype "input"))
      (node (ref "C12") (pin "2") (pinfunction "2_2") (pintype "input"))
      (node (ref "C14") (pin "2") (pinfunction "2_2") (pintype "input"))
      (node (ref "C18") (pin "2") (pinfunction "2_2") (pintype "input"))
      (node (ref "C19") (pin "2") (pinfunction "2_2") (pintype "input"))
      (node (ref "C20") (pin "2") (pinfunction "2_2") (pintype "input"))
      (node (ref "C7") (pin "2") (pinfunction "2_2") (pintype "input"))
      (node (ref "C8") (pin "2") (pinfunction "2_2") (pintype "input"))
      (node (ref "H1") (pin "1") (pinfunction "GND_1") (pintype "input"))
      (node (ref "J1") (pin "2") (pinfunction "2_2") (pintype "input"))
      (node (ref "Q2") (pin "1") (pinfunction "S1_1") (pintype "input"))
      (node (ref "Q3") (pin "2") (pinfunction "VSS_2") (pintype "input"))
      (node (ref "R13") (pin "2") (pinfunction "2_2") (pintype "input"))
      (node (ref "R20") (pin "1") (pinfunction "1_1") (pintype "input"))
      (node (ref "R3") (pin "2") (pinfunction "2_2") (pintype "input"))
      (node (ref "R4") (pin "2") (pinfunction "2_2") (pintype "input"))
      (node (ref "R40") (pin "1") (pinfunction "1_1") (pintype "input"))
      (node (ref "R5") (pin "1") (pinfunction "1_1") (pintype "input"))
      (node (ref "R8") (pin "1") (pinfunction "1_1") (pintype "input"))
      (node (ref "R9") (pin "2") (pinfunction "2_2") (pintype "input"))
      (node (ref "RJ1") (pin "8") (pinfunction "8_8") (pintype "input"))
      (node (ref "RJ2") (pin "8") (pinfunction "8_8") (pintype "input"))
      (node (ref "RJ3") (pin "8") (pinfunction "8_8") (pintype "input"))
      (node (ref "RJ4") (pin "8") (pinfunction "8_8") (pintype "input"))
      (node (ref "RJ5") (pin "8") (pinfunction "8_8") (pintype "input"))
      (node (ref "RJ6") (pin "8") (pinfunction "8_8") (pintype "input"))
      (node (ref "RJ7") (pin "8") (pinfunction "8_8") (pintype "input"))
      (node (ref "RJ8") (pin "8") (pinfunction "8_8") (pintype "input"))
      (node (ref "SW1") (pin "2") (pinfunction "2_2") (pintype "input"))
      (node (ref "U1") (pin "9") (pinfunction "GND_9") (pintype "input"))
      (node (ref "U10") (pin "6") (pinfunction "GND_6") (pintype "input"))
      (node (ref "U10") (pin "7") (pinfunction "EP_7") (pintype "input"))
      (node (ref "U11") (pin "6") (pinfunction "GND_6") (pintype "input"))
      (node (ref "U11") (pin "7") (pinfunction "EP_7") (pintype "input"))
      (node (ref "U12") (pin "6") (pinfunction "GND_6") (pintype "input"))
      (node (ref "U12") (pin "7") (pinfunction "EP_7") (pintype "input"))
      (node (ref "U13") (pin "6") (pinfunction "GND_6") (pintype "input"))
      (node (ref "U13") (pin "7") (pinfunction "EP_7") (pintype "input"))
      (node (ref "U14") (pin "6") (pinfunction "GND_6") (pintype "input"))
      (node (ref "U14") (pin "7") (pinfunction "EP_7") (pintype "input"))
      (node (ref "U15") (pin "6") (pinfunction "GND_6") (pintype "input"))
      (node (ref "U15") (pin "7") (pinfunction "EP_7") (pintype "input"))
      (node (ref "U16") (pin "6") (pinfunction "GND_6") (pintype "input"))
      (node (ref "U16") (pin "7") (pinfunction "EP_7") (pintype "input"))
      (node (ref "U2") (pin "12") (pinfunction "GND_12") (pintype "input"))
      (node (ref "U3") (pin "6") (pinfunction "GND_6") (pintype "input"))
      (node (ref "U3") (pin "7") (pinfunction "EP_7") (pintype "input"))
      (node (ref "U4") (pin "1") (pinfunction "GND_1") (pintype "input"))
      (node (ref "U7") (pin "10") (pinfunction "VSS_10") (pintype "input"))
      (node (ref "U8") (pin "1") (pinfunction "TEMP_1") (pintype "input"))
      (node (ref "U8") (pin "3") (pinfunction "GND_3") (pintype "input"))
      (node (ref "U8") (pin "9") (pinfunction "EP_9") (pintype "input"))
      (node (ref "U9") (pin "6") (pinfunction "GND_6") (pintype "input"))
      (node (ref "U9") (pin "7") (pinfunction "EP_7") (pintype "input"))
      (node (ref "USB1") (pin "0") (pinfunction "SHELL_0") (pintype "input"))
      (node (ref "USB1") (pin "A1B12") (pinfunction "GND_A1B12") (pintype "input"))
      (node (ref "USB1") (pin "B1A12") (pinfunction "GND_B1A12") (pintype "input"))
    )
    (net (code "13") (name "GPA0") (class "Default")
      (node (ref "RJ1") (pin "5") (pinfunction "5_5") (pintype "input"))
      (node (ref "U7") (pin "21") (pinfunction "GPA0_21") (pintype "input"))
    )
    (net (code "14") (name "GPA1") (class "Default")
      (node (ref "RJ2") (pin "5") (pinfunction "5_5") (pintype "input"))
      (node (ref "U7") (pin "22") (pinfunction "GPA1_22") (pintype "input"))
    )
    (net (code "15") (name "GPA2") (class "Default")
      (node (ref "RJ4") (pin "5") (pinfunction "5_5") (pintype "input"))
      (node (ref "U7") (pin "23") (pinfunction "GPA2_23") (pintype "input"))
    )
    (net (code "16") (name "GPA3") (class "Default")
      (node (ref "RJ3") (pin "5") (pinfunction "5_5") (pintype "input"))
      (node (ref "U7") (pin "24") (pinfunction "GPA3_24") (pintype "input"))
    )
    (net (code "17") (name "GPA4") (class "Default")
      (node (ref "RJ8") (pin "5") (pinfunction "5_5") (pintype "input"))
      (node (ref "U7") (pin "25") (pinfunction "GPA4_25") (pintype "input"))
    )
    (net (code "18") (name "GPA5") (class "Default")
      (node (ref "RJ7") (pin "5") (pinfunction "5_5") (pintype "input"))
      (node (ref "U7") (pin "26") (pinfunction "GPA5_26") (pintype "input"))
    )
    (net (code "19") (name "GPA6") (class "Default")
      (node (ref "RJ5") (pin "5") (pinfunction "5_5") (pintype "input"))
      (node (ref "U7") (pin "27") (pinfunction "GPA6_27") (pintype "input"))
    )
    (net (code "20") (name "GPA7") (class "Default")
      (node (ref "RJ6") (pin "5") (pinfunction "5_5") (pintype "input"))
      (node (ref "U7") (pin "28") (pinfunction "GPA7_28") (pintype "input"))
    )
    (net (code "21") (name "GPB0") (class "Default")
      (node (ref "RJ1") (pin "4") (pinfunction "4_4") (pintype "input"))
      (node (ref "U7") (pin "1") (pinfunction "GPB0_1") (pintype "input"))
    )
    (net (code "22") (name "GPB1") (class "Default")
      (node (ref "RJ2") (pin "4") (pinfunction "4_4") (pintype "input"))
      (node (ref "U7") (pin "2") (pinfunction "GPB1_2") (pintype "input"))
    )
    (net (code "23") (name "GPB2") (class "Default")
      (node (ref "RJ4") (pin "4") (pinfunction "4_4") (pintype "input"))
      (node (ref "U7") (pin "3") (pinfunction "GPB2_3") (pintype "input"))
    )
    (net (code "24") (name "GPB3") (class "Default")
      (node (ref "RJ3") (pin "4") (pinfunction "4_4") (pintype "input"))
      (node (ref "U7") (pin "4") (pinfunction "GPB3_4") (pintype "input"))
    )
    (net (code "25") (name "GPB4") (class "Default")
      (node (ref "RJ8") (pin "4") (pinfunction "4_4") (pintype "input"))
      (node (ref "U7") (pin "5") (pinfunction "GPB4_5") (pintype "input"))
    )
    (net (code "26") (name "GPB5") (class "Default")
      (node (ref "RJ7") (pin "4") (pinfunction "4_4") (pintype "input"))
      (node (ref "U7") (pin "6") (pinfunction "GPB5_6") (pintype "input"))
    )
    (net (code "27") (name "GPB6") (class "Default")
      (node (ref "RJ5") (pin "4") (pinfunction "4_4") (pintype "input"))
      (node (ref "U7") (pin "7") (pinfunction "GPB6_7") (pintype "input"))
    )
    (net (code "28") (name "GPB7") (class "Default")
      (node (ref "RJ6") (pin "4") (pinfunction "4_4") (pintype "input"))
      (node (ref "U7") (pin "8") (pinfunction "GPB7_8") (pintype "input"))
    )
    (net (code "29") (name "GPI0") (class "Default")
      (node (ref "Q1") (pin "3") (pinfunction "C_3") (pintype "input"))
      (node (ref "R6") (pin "2") (pinfunction "2_2") (pintype "input"))
      (node (ref "U1") (pin "12") (pinfunction "GPIO0_12") (pintype "input"))
    )
    (net (code "30") (name "GPI2") (class "Default")
      (node (ref "LED2") (pin "1") (pinfunction "1_1") (pintype "input"))
      (node (ref "R19") (pin "2") (pinfunction "2_2") (pintype "input"))
      (node (ref "U1") (pin "11") (pinfunction "GPIO2_11") (pintype "input"))
    )
    (net (code "31") (name "GPI015") (class "Default")
      (node (ref "R20") (pin "2") (pinfunction "2_2") (pintype "input"))
      (node (ref "U1") (pin "10") (pinfunction "GPIO15_10") (pintype "input"))
    )
    (net (code "32") (name "Net-(D1-C)") (class "Default")
      (node (ref "C20") (pin "1") (pinfunction "1_1") (pintype "input"))
      (node (ref "D1") (pin "1") (pinfunction "C_1") (pintype "input"))
      (node (ref "D4") (pin "1") (pinfunction "C_1") (pintype "input"))
      (node (ref "H1") (pin "3") (pinfunction "VIN_3") (pintype "input"))
      (node (ref "Q3") (pin "1") (pinfunction "VIN_1") (pintype "input"))
    )
    (net (code "33") (name "Net-(H1-EN{slash}CE)") (class "Default")
      (node (ref "H1") (pin "2") (pinfunction "EN/CE_2") (pintype "input"))
      (node (ref "Q3") (pin "3") (pinfunction "CE_3") (pintype "input"))
    )
    (net (code "34") (name "Net-(LED1-Pad2)") (class "Default")
      (node (ref "LED1") (pin "2") (pinfunction "2_2") (pintype "input"))
      (node (ref "R15") (pin "1") (pinfunction "1_1") (pintype "input"))
    )
    (net (code "35") (name "Net-(LED2-Pad2)") (class "Default")
      (node (ref "LED2") (pin "2") (pinfunction "2_2") (pintype "input"))
      (node (ref "R38") (pin "1") (pinfunction "1_1") (pintype "input"))
    )
    (net (code "36") (name "Net-(LED4-Pad2)") (class "Default")
      (node (ref "LED4") (pin "2") (pinfunction "2_2") (pintype "input"))
      (node (ref "R14") (pin "1") (pinfunction "1_1") (pintype "input"))
    )
    (net (code "37") (name "Net-(Q2-G1)") (class "Default")
      (node (ref "Q2") (pin "6") (pinfunction "G1_6") (pintype "input"))
      (node (ref "U6") (pin "3") (pinfunction "OC_3") (pintype "input"))
    )
    (net (code "38") (name "Net-(Q2-G2)") (class "Default")
      (node (ref "Q2") (pin "4") (pinfunction "G2_4") (pintype "input"))
      (node (ref "U6") (pin "1") (pinfunction "OD_1") (pintype "input"))
    )
    (net (code "39") (name "Net-(U1-ADC)") (class "Default")
      (node (ref "R22") (pin "2") (pinfunction "2_2") (pintype "input"))
      (node (ref "U1") (pin "2") (pinfunction "ADC_2") (pintype "input"))
    )
    (net (code "40") (name "Net-(U1-EN)") (class "Default")
      (node (ref "R7") (pin "2") (pinfunction "2_2") (pintype "input"))
      (node (ref "U1") (pin "3") (pinfunction "EN_3") (pintype "input"))
    )
    (net (code "41") (name "Net-(U2-A0)") (class "Default")
      (node (ref "R3") (pin "1") (pinfunction "1_1") (pintype "input"))
      (node (ref "U2") (pin "1") (pinfunction "A0_1") (pintype "input"))
    )
    (net (code "42") (name "Net-(U2-A1)") (class "Default")
      (node (ref "R4") (pin "1") (pinfunction "1_1") (pintype "input"))
      (node (ref "U2") (pin "2") (pinfunction "A1_2") (pintype "input"))
    )
    (net (code "43") (name "Net-(U2-A2)") (class "Default")
      (node (ref "R5") (pin "2") (pinfunction "2_2") (pintype "input"))
      (node (ref "U2") (pin "21") (pinfunction "A2_21") (pintype "input"))
    )
    (net (code "44") (name "Net-(U4-RXD)") (class "Default")
      (node (ref "R21") (pin "2") (pinfunction "2_2") (pintype "input"))
      (node (ref "U4") (pin "3") (pinfunction "RXD_3") (pintype "input"))
    )
    (net (code "45") (name "Net-(U6-CSI)") (class "Default")
      (node (ref "R13") (pin "1") (pinfunction "1_1") (pintype "input"))
      (node (ref "U6") (pin "2") (pinfunction "CSI_2") (pintype "input"))
    )
    (net (code "46") (name "Net-(U6-VDD)") (class "Default")
      (node (ref "C13") (pin "1") (pinfunction "1_1") (pintype "input"))
      (node (ref "R11") (pin "1") (pinfunction "1_1") (pintype "input"))
      (node (ref "U6") (pin "5") (pinfunction "VDD_5") (pintype "input"))
    )
    (net (code "47") (name "Net-(U8-CHRG#)") (class "Default")
      (node (ref "R14") (pin "2") (pinfunction "2_2") (pintype "input"))
      (node (ref "U8") (pin "7") (pinfunction "CHRG#_7") (pintype "input"))
    )
    (net (code "48") (name "Net-(U8-PROG)") (class "Default")
      (node (ref "R40") (pin "2") (pinfunction "2_2") (pintype "input"))
      (node (ref "U8") (pin "2") (pinfunction "PROG_2") (pintype "input"))
    )
    (net (code "49") (name "Net-(U8-STDBY#)") (class "Default")
      (node (ref "R15") (pin "2") (pinfunction "2_2") (pintype "input"))
      (node (ref "U8") (pin "6") (pinfunction "STDBY#_6") (pintype "input"))
    )
    (net (code "50") (name "Net-(USB1-CC1)") (class "Default")
      (node (ref "R9") (pin "1") (pinfunction "1_1") (pintype "input"))
      (node (ref "USB1") (pin "A5") (pinfunction "CC1_A5") (pintype "input"))
    )
    (net (code "51") (name "Net-(USB1-CC2)") (class "Default")
      (node (ref "R8") (pin "2") (pinfunction "2_2") (pintype "input"))
      (node (ref "USB1") (pin "B5") (pinfunction "CC2_B5") (pintype "input"))
    )
    (net (code "52") (name "RST") (class "Default")
      (node (ref "C19") (pin "1") (pinfunction "1_1") (pintype "input"))
      (node (ref "Q1") (pin "6") (pinfunction "C_6") (pintype "input"))
      (node (ref "SW1") (pin "1") (pinfunction "1_1") (pintype "input"))
      (node (ref "U1") (pin "1") (pinfunction "RST_1") (pintype "input"))
    )
    (net (code "53") (name "RTS") (class "Default")
      (node (ref "Q1") (pin "1") (pinfunction "E_1") (pintype "input"))
      (node (ref "Q1") (pin "5") (pinfunction "B_5") (pintype "input"))
      (node (ref "U4") (pin "14") (pinfunction "RTS#_14") (pintype "input"))
    )
    (net (code "54") (name "RX") (class "Default")
      (node (ref "U1") (pin "15") (pinfunction "RXD0_15") (pintype "input"))
      (node (ref "U4") (pin "2") (pinfunction "TXD_2") (pintype "input"))
    )
    (net (code "55") (name "SC0") (class "Default")
      (node (ref "R2") (pin "2") (pinfunction "2_2") (pintype "input"))
      (node (ref "RJ1") (pin "6") (pinfunction "6_6") (pintype "input"))
      (node (ref "U2") (pin "5") (pinfunction "SC0_5") (pintype "input"))
      (node (ref "U9") (pin "5") (pinfunction "BUS2_5") (pintype "input"))
    )
    (net (code "56") (name "SC1") (class "Default")
      (node (ref "R25") (pin "2") (pinfunction "2_2") (pintype "input"))
      (node (ref "RJ2") (pin "6") (pinfunction "6_6") (pintype "input"))
      (node (ref "U10") (pin "5") (pinfunction "BUS2_5") (pintype "input"))
      (node (ref "U2") (pin "7") (pinfunction "SC1_7") (pintype "input"))
    )
    (net (code "57") (name "SC2") (class "Default")
      (node (ref "R27") (pin "2") (pinfunction "2_2") (pintype "input"))
      (node (ref "RJ4") (pin "6") (pinfunction "6_6") (pintype "input"))
      (node (ref "U11") (pin "5") (pinfunction "BUS2_5") (pintype "input"))
      (node (ref "U2") (pin "9") (pinfunction "SC2_9") (pintype "input"))
    )
    (net (code "58") (name "SC3") (class "Default")
      (node (ref "R29") (pin "2") (pinfunction "2_2") (pintype "input"))
      (node (ref "RJ3") (pin "6") (pinfunction "6_6") (pintype "input"))
      (node (ref "U12") (pin "5") (pinfunction "BUS2_5") (pintype "input"))
      (node (ref "U2") (pin "11") (pinfunction "SC3_11") (pintype "input"))
    )
    (net (code "59") (name "SC4") (class "Default")
      (node (ref "R31") (pin "2") (pinfunction "2_2") (pintype "input"))
      (node (ref "RJ8") (pin "6") (pinfunction "6_6") (pintype "input"))
      (node (ref "U13") (pin "5") (pinfunction "BUS2_5") (pintype "input"))
      (node (ref "U2") (pin "14") (pinfunction "SC4_14") (pintype "input"))
    )
    (net (code "60") (name "SC5") (class "Default")
      (node (ref "R33") (pin "2") (pinfunction "2_2") (pintype "input"))
      (node (ref "RJ7") (pin "6") (pinfunction "6_6") (pintype "input"))
      (node (ref "U14") (pin "5") (pinfunction "BUS2_5") (pintype "input"))
      (node (ref "U2") (pin "16") (pinfunction "SC5_16") (pintype "input"))
    )
    (net (code "61") (name "SC6") (class "Default")
      (node (ref "R35") (pin "2") (pinfunction "2_2") (pintype "input"))
      (node (ref "RJ5") (pin "6") (pinfunction "6_6") (pintype "input"))
      (node (ref "U15") (pin "5") (pinfunction "BUS2_5") (pintype "input"))
      (node (ref "U2") (pin "18") (pinfunction "SC6_18") (pintype "input"))
    )
    (net (code "62") (name "SC7") (class "Default")
      (node (ref "R37") (pin "2") (pinfunction "2_2") (pintype "input"))
      (node (ref "RJ6") (pin "6") (pinfunction "6_6") (pintype "input"))
      (node (ref "U16") (pin "5") (pinfunction "BUS2_5") (pintype "input"))
      (node (ref "U2") (pin "20") (pinfunction "SC7_20") (pintype "input"))
    )
    (net (code "63") (name "SCL") (class "Default")
      (node (ref "J1") (pin "3") (pinfunction "3_3") (pintype "input"))
      (node (ref "R10") (pin "2") (pinfunction "2_2") (pintype "input"))
      (node (ref "U1") (pin "14") (pinfunction "GPIO5_14") (pintype "input"))
      (node (ref "U2") (pin "22") (pinfunction "SCL_22") (pintype "input"))
      (node (ref "U3") (pin "5") (pinfunction "BUS2_5") (pintype "input"))
      (node (ref "U7") (pin "12") (pinfunction "SCL_12") (pintype "input"))
    )
    (net (code "64") (name "SD0") (class "Default")
      (node (ref "R23") (pin "2") (pinfunction "2_2") (pintype "input"))
      (node (ref "RJ1") (pin "3") (pinfunction "3_3") (pintype "input"))
      (node (ref "U2") (pin "4") (pinfunction "SD0_4") (pintype "input"))
      (node (ref "U9") (pin "4") (pinfunction "BUS1_4") (pintype "input"))
    )
    (net (code "65") (name "SD1") (class "Default")
      (node (ref "R24") (pin "2") (pinfunction "2_2") (pintype "input"))
      (node (ref "RJ2") (pin "3") (pinfunction "3_3") (pintype "input"))
      (node (ref "U10") (pin "4") (pinfunction "BUS1_4") (pintype "input"))
      (node (ref "U2") (pin "6") (pinfunction "SD1_6") (pintype "input"))
    )
    (net (code "66") (name "SD2") (class "Default")
      (node (ref "R26") (pin "2") (pinfunction "2_2") (pintype "input"))
      (node (ref "RJ4") (pin "3") (pinfunction "3_3") (pintype "input"))
      (node (ref "U11") (pin "4") (pinfunction "BUS1_4") (pintype "input"))
      (node (ref "U2") (pin "8") (pinfunction "SD2_8") (pintype "input"))
    )
    (net (code "67") (name "SD3") (class "Default")
      (node (ref "R28") (pin "2") (pinfunction "2_2") (pintype "input"))
      (node (ref "RJ3") (pin "3") (pinfunction "3_3") (pintype "input"))
      (node (ref "U12") (pin "4") (pinfunction "BUS1_4") (pintype "input"))
      (node (ref "U2") (pin "10") (pinfunction "SD3_10") (pintype "input"))
    )
    (net (code "68") (name "SD4") (class "Default")
      (node (ref "R30") (pin "2") (pinfunction "2_2") (pintype "input"))
      (node (ref "RJ8") (pin "3") (pinfunction "3_3") (pintype "input"))
      (node (ref "U13") (pin "4") (pinfunction "BUS1_4") (pintype "input"))
      (node (ref "U2") (pin "13") (pinfunction "SD4_13") (pintype "input"))
    )
    (net (code "69") (name "SD5") (class "Default")
      (node (ref "R32") (pin "2") (pinfunction "2_2") (pintype "input"))
      (node (ref "RJ7") (pin "3") (pinfunction "3_3") (pintype "input"))
      (node (ref "U14") (pin "4") (pinfunction "BUS1_4") (pintype "input"))
      (node (ref "U2") (pin "15") (pinfunction "SD5_15") (pintype "input"))
    )
    (net (code "70") (name "SD6") (class "Default")
      (node (ref "R34") (pin "2") (pinfunction "2_2") (pintype "input"))
      (node (ref "RJ5") (pin "3") (pinfunction "3_3") (pintype "input"))
      (node (ref "U15") (pin "4") (pinfunction "BUS1_4") (pintype "input"))
      (node (ref "U2") (pin "17") (pinfunction "SD6_17") (pintype "input"))
    )
    (net (code "71") (name "SD7") (class "Default")
      (node (ref "R36") (pin "2") (pinfunction "2_2") (pintype "input"))
      (node (ref "RJ6") (pin "3") (pinfunction "3_3") (pintype "input"))
      (node (ref "U16") (pin "4") (pinfunction "BUS1_4") (pintype "input"))
      (node (ref "U2") (pin "19") (pinfunction "SD7_19") (pintype "input"))
    )
    (net (code "72") (name "SDA") (class "Default")
      (node (ref "J1") (pin "4") (pinfunction "4_4") (pintype "input"))
      (node (ref "R12") (pin "2") (pinfunction "2_2") (pintype "input"))
      (node (ref "U1") (pin "13") (pinfunction "GPIO4_13") (pintype "input"))
      (node (ref "U2") (pin "23") (pinfunction "SDA_23") (pintype "input"))
      (node (ref "U3") (pin "4") (pinfunction "BUS1_4") (pintype "input"))
      (node (ref "U7") (pin "13") (pinfunction "SDA_13") (pintype "input"))
    )
    (net (code "73") (name "TX") (class "Default")
      (node (ref "R21") (pin "1") (pinfunction "1_1") (pintype "input"))
      (node (ref "U1") (pin "16") (pinfunction "TXD0_16") (pintype "input"))
    )
    (net (code "74") (name "unconnected-(Q2-D12-Pad2)") (class "Default")
      (node (ref "Q2") (pin "2") (pinfunction "D12_2") (pintype "input+no_connect"))
    )
    (net (code "75") (name "unconnected-(Q2-D12-Pad5)") (class "Default")
      (node (ref "Q2") (pin "5") (pinfunction "D12_5") (pintype "input+no_connect"))
    )
    (net (code "76") (name "unconnected-(Q3-NC-Pad4)") (class "Default")
      (node (ref "Q3") (pin "4") (pinfunction "NC_4") (pintype "input+no_connect"))
    )
    (net (code "77") (name "unconnected-(RJ1-Pad2)") (class "Default")
      (node (ref "RJ1") (pin "2") (pinfunction "2_2") (pintype "input+no_connect"))
    )
    (net (code "78") (name "unconnected-(RJ1-Pad7)") (class "Default")
      (node (ref "RJ1") (pin "7") (pinfunction "7_7") (pintype "input+no_connect"))
    )
    (net (code "79") (name "unconnected-(RJ2-Pad2)") (class "Default")
      (node (ref "RJ2") (pin "2") (pinfunction "2_2") (pintype "input+no_connect"))
    )
    (net (code "80") (name "unconnected-(RJ2-Pad7)") (class "Default")
      (node (ref "RJ2") (pin "7") (pinfunction "7_7") (pintype "input+no_connect"))
    )
    (net (code "81") (name "unconnected-(RJ3-Pad2)") (class "Default")
      (node (ref "RJ3") (pin "2") (pinfunction "2_2") (pintype "input+no_connect"))
    )
    (net (code "82") (name "unconnected-(RJ3-Pad7)") (class "Default")
      (node (ref "RJ3") (pin "7") (pinfunction "7_7") (pintype "input+no_connect"))
    )
    (net (code "83") (name "unconnected-(RJ4-Pad2)") (class "Default")
      (node (ref "RJ4") (pin "2") (pinfunction "2_2") (pintype "input+no_connect"))
    )
    (net (code "84") (name "unconnected-(RJ4-Pad7)") (class "Default")
      (node (ref "RJ4") (pin "7") (pinfunction "7_7") (pintype "input+no_connect"))
    )
    (net (code "85") (name "unconnected-(RJ5-Pad2)") (class "Default")
      (node (ref "RJ5") (pin "2") (pinfunction "2_2") (pintype "input+no_connect"))
    )
    (net (code "86") (name "unconnected-(RJ5-Pad7)") (class "Default")
      (node (ref "RJ5") (pin "7") (pinfunction "7_7") (pintype "input+no_connect"))
    )
    (net (code "87") (name "unconnected-(RJ6-Pad2)") (class "Default")
      (node (ref "RJ6") (pin "2") (pinfunction "2_2") (pintype "input+no_connect"))
    )
    (net (code "88") (name "unconnected-(RJ6-Pad7)") (class "Default")
      (node (ref "RJ6") (pin "7") (pinfunction "7_7") (pintype "input+no_connect"))
    )
    (net (code "89") (name "unconnected-(RJ7-Pad2)") (class "Default")
      (node (ref "RJ7") (pin "2") (pinfunction "2_2") (pintype "input+no_connect"))
    )
    (net (code "90") (name "unconnected-(RJ7-Pad7)") (class "Default")
      (node (ref "RJ7") (pin "7") (pinfunction "7_7") (pintype "input+no_connect"))
    )
    (net (code "91") (name "unconnected-(RJ8-Pad2)") (class "Default")
      (node (ref "RJ8") (pin "2") (pinfunction "2_2") (pintype "input+no_connect"))
    )
    (net (code "92") (name "unconnected-(RJ8-Pad7)") (class "Default")
      (node (ref "RJ8") (pin "7") (pinfunction "7_7") (pintype "input+no_connect"))
    )
    (net (code "93") (name "unconnected-(U1-CS0-Pad17)") (class "Default")
      (node (ref "U1") (pin "17") (pinfunction "CS0_17") (pintype "input+no_connect"))
    )
    (net (code "94") (name "unconnected-(U1-GPIO9-Pad19)") (class "Default")
      (node (ref "U1") (pin "19") (pinfunction "GPIO9_19") (pintype "input+no_connect"))
    )
    (net (code "95") (name "unconnected-(U1-GPIO10-Pad20)") (class "Default")
      (node (ref "U1") (pin "20") (pinfunction "GPIO10_20") (pintype "input+no_connect"))
    )
    (net (code "96") (name "unconnected-(U1-GPIO16-Pad4)") (class "Default")
      (node (ref "U1") (pin "4") (pinfunction "GPIO16_4") (pintype "input+no_connect"))
    )
    (net (code "97") (name "unconnected-(U1-MISO-Pad18)") (class "Default")
      (node (ref "U1") (pin "18") (pinfunction "MISO_18") (pintype "input+no_connect"))
    )
    (net (code "98") (name "unconnected-(U1-MOSI-Pad21)") (class "Default")
      (node (ref "U1") (pin "21") (pinfunction "MOSI_21") (pintype "input+no_connect"))
    )
    (net (code "99") (name "unconnected-(U1-SCLK-Pad22)") (class "Default")
      (node (ref "U1") (pin "22") (pinfunction "SCLK_22") (pintype "input+no_connect"))
    )
    (net (code "100") (name "unconnected-(U3-NC-Pad2)") (class "Default")
      (node (ref "U3") (pin "2") (pinfunction "NC_2") (pintype "input+no_connect"))
    )
    (net (code "101") (name "unconnected-(U4-CTS#-Pad9)") (class "Default")
      (node (ref "U4") (pin "9") (pinfunction "CTS#_9") (pintype "input+no_connect"))
    )
    (net (code "102") (name "unconnected-(U4-DCD#-Pad12)") (class "Default")
      (node (ref "U4") (pin "12") (pinfunction "DCD#_12") (pintype "input+no_connect"))
    )
    (net (code "103") (name "unconnected-(U4-DSR#-Pad10)") (class "Default")
      (node (ref "U4") (pin "10") (pinfunction "DSR#_10") (pintype "input+no_connect"))
    )
    (net (code "104") (name "unconnected-(U4-NC.-Pad7)") (class "Default")
      (node (ref "U4") (pin "7") (pinfunction "NC._7") (pintype "input+no_connect"))
    )
    (net (code "105") (name "unconnected-(U4-NC.-Pad8)") (class "Default")
      (node (ref "U4") (pin "8") (pinfunction "NC._8") (pintype "input+no_connect"))
    )
    (net (code "106") (name "unconnected-(U4-R232-Pad15)") (class "Default")
      (node (ref "U4") (pin "15") (pinfunction "R232_15") (pintype "input+no_connect"))
    )
    (net (code "107") (name "unconnected-(U4-RI#-Pad11)") (class "Default")
      (node (ref "U4") (pin "11") (pinfunction "RI#_11") (pintype "input+no_connect"))
    )
    (net (code "108") (name "unconnected-(U6-TD-Pad4)") (class "Default")
      (node (ref "U6") (pin "4") (pinfunction "TD_4") (pintype "input+no_connect"))
    )
    (net (code "109") (name "unconnected-(U7-NC-Pad11)") (class "Default")
      (node (ref "U7") (pin "11") (pinfunction "NC_11") (pintype "input+no_connect"))
    )
    (net (code "110") (name "unconnected-(U7-NC-Pad14)") (class "Default")
      (node (ref "U7") (pin "14") (pinfunction "NC_14") (pintype "input+no_connect"))
    )
    (net (code "111") (name "unconnected-(U9-NC-Pad2)") (class "Default")
      (node (ref "U9") (pin "2") (pinfunction "NC_2") (pintype "input+no_connect"))
    )
    (net (code "112") (name "unconnected-(U10-NC-Pad2)") (class "Default")
      (node (ref "U10") (pin "2") (pinfunction "NC_2") (pintype "input+no_connect"))
    )
    (net (code "113") (name "unconnected-(U11-NC-Pad2)") (class "Default")
      (node (ref "U11") (pin "2") (pinfunction "NC_2") (pintype "input+no_connect"))
    )
    (net (code "114") (name "unconnected-(U12-NC-Pad2)") (class "Default")
      (node (ref "U12") (pin "2") (pinfunction "NC_2") (pintype "input+no_connect"))
    )
    (net (code "115") (name "unconnected-(U13-NC-Pad2)") (class "Default")
      (node (ref "U13") (pin "2") (pinfunction "NC_2") (pintype "input+no_connect"))
    )
    (net (code "116") (name "unconnected-(U14-NC-Pad2)") (class "Default")
      (node (ref "U14") (pin "2") (pinfunction "NC_2") (pintype "input+no_connect"))
    )
    (net (code "117") (name "unconnected-(U15-NC-Pad2)") (class "Default")
      (node (ref "U15") (pin "2") (pinfunction "NC_2") (pintype "input+no_connect"))
    )
    (net (code "118") (name "unconnected-(U16-NC-Pad2)") (class "Default")
      (node (ref "U16") (pin "2") (pinfunction "NC_2") (pintype "input+no_connect"))
    )
    (net (code "119") (name "unconnected-(USB1-SBU1-PadA8)") (class "Default")
      (node (ref "USB1") (pin "A8") (pinfunction "SBU1_A8") (pintype "input+no_connect"))
    )
    (net (code "120") (name "unconnected-(USB1-SBU2-PadB8)") (class "Default")
      (node (ref "USB1") (pin "B8") (pinfunction "SBU2_B8") (pintype "input+no_connect"))
    )
  )
)
